# FPGA_S6.net
KiCad netlist of a schematic drawn in EAGLE
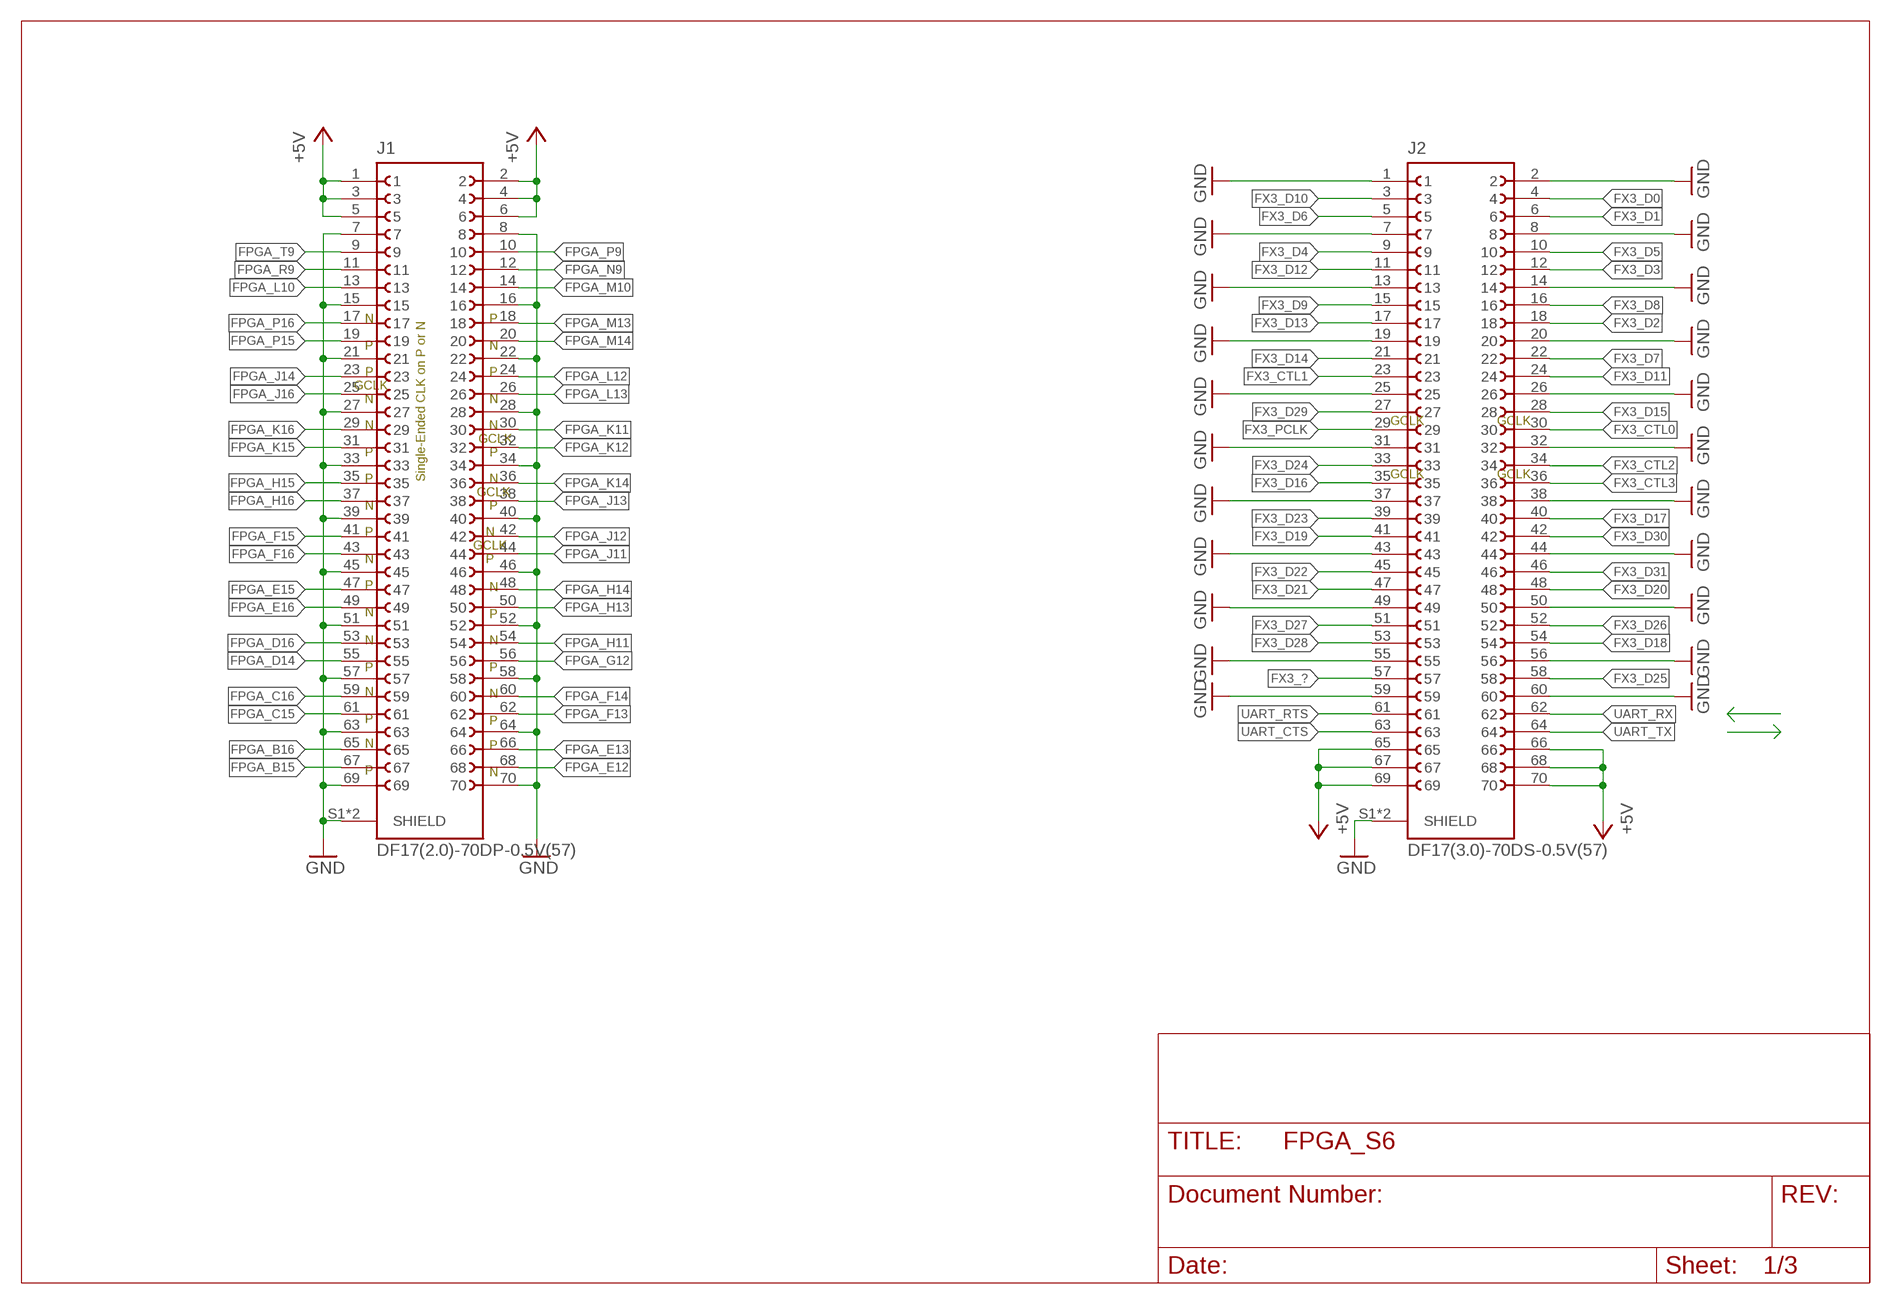
[diagram p0: schematic, sheet 1]
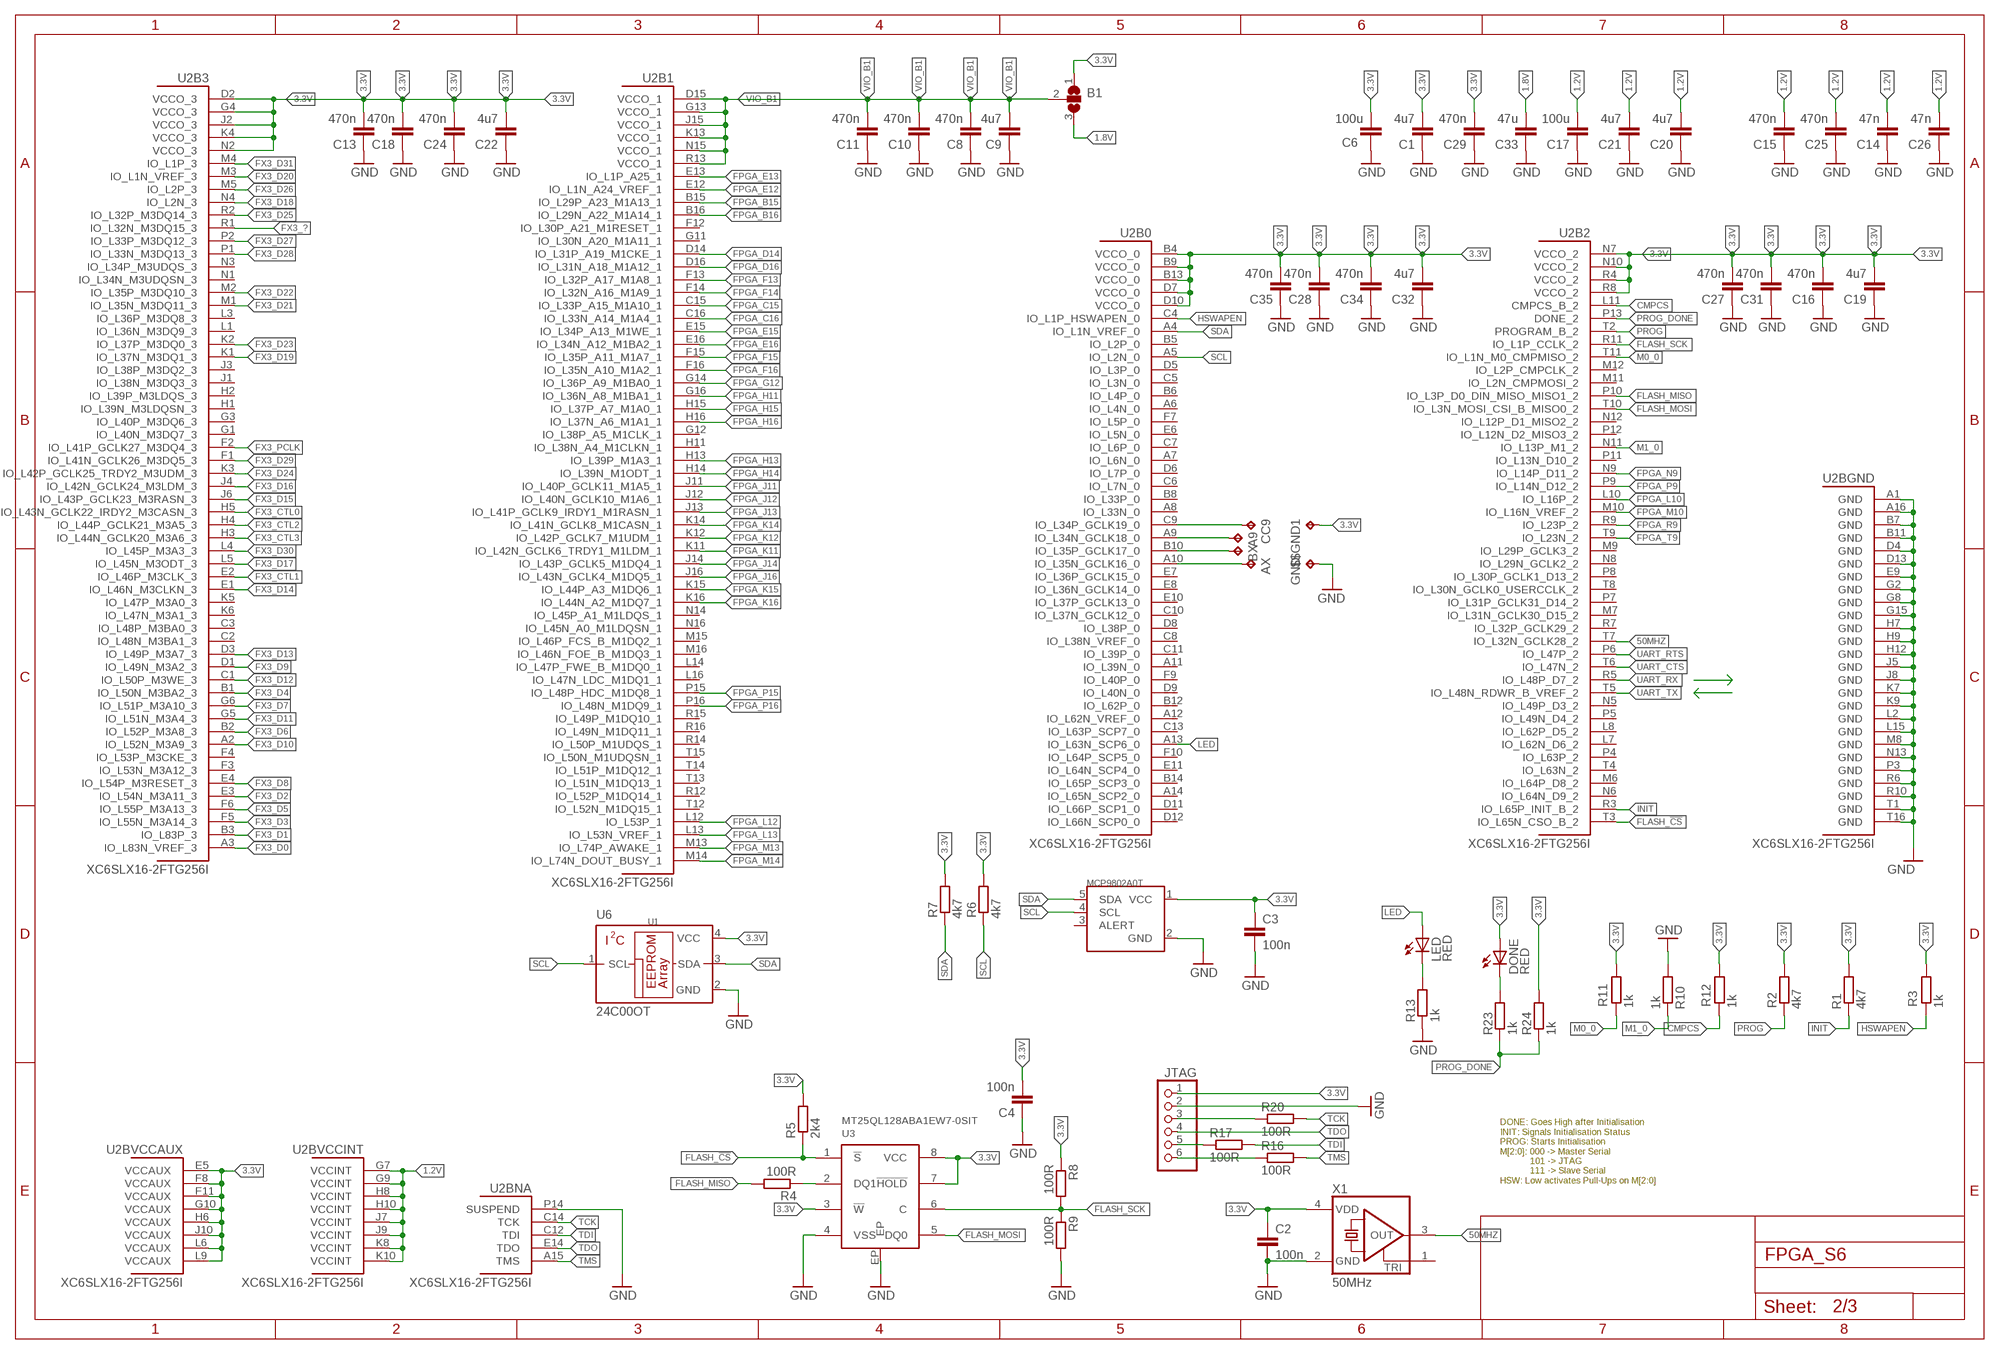
[diagram p1: schematic, sheet 2]
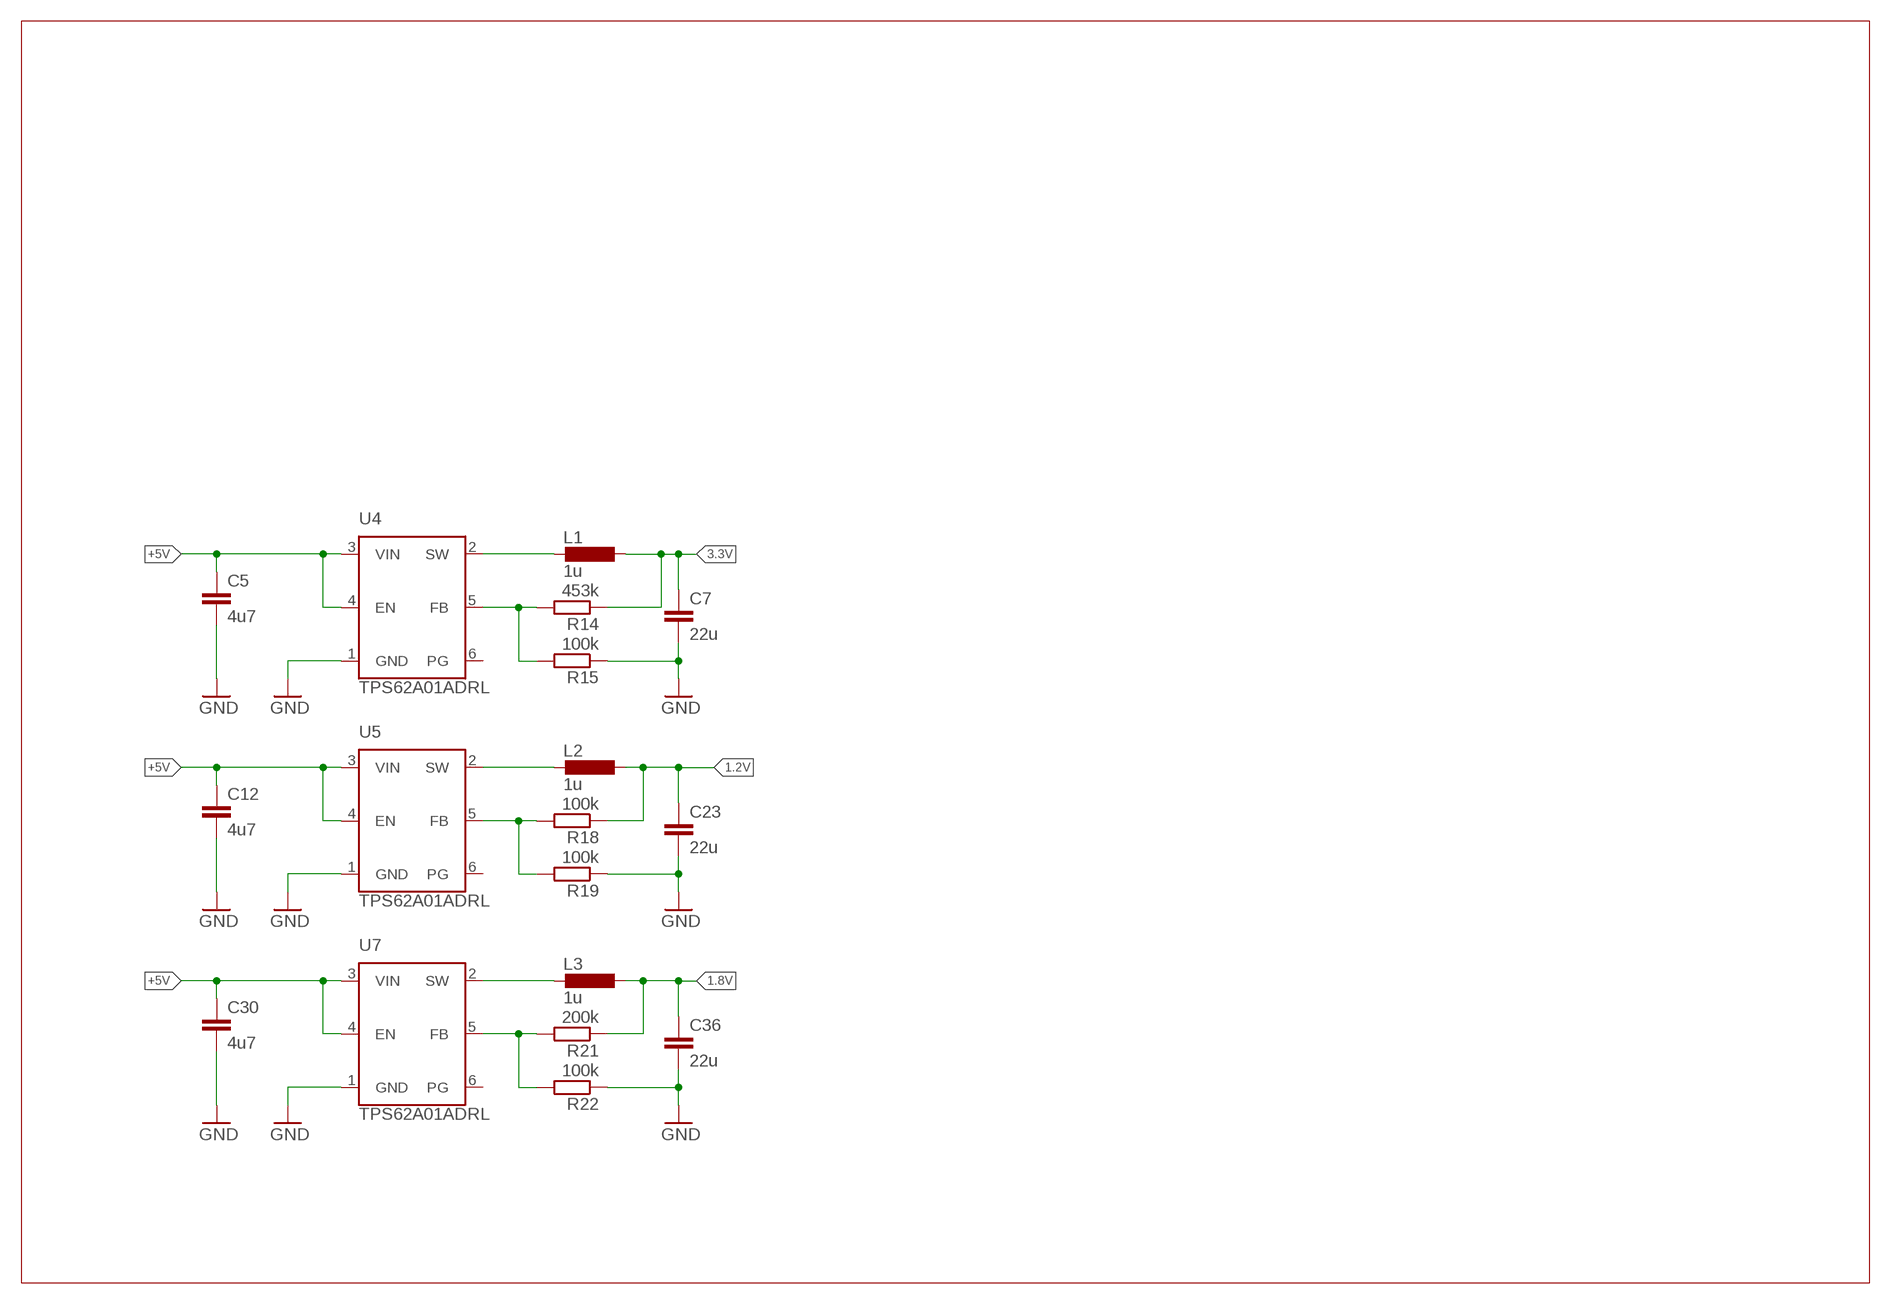
[diagram p2: schematic, sheet 3]

(export (version "E")
  (design (tool "Eeschema 10.0.6"))
  (components
    (comp (ref "$$GND1")
      (value "TPTP15R")
      (footprint "eagle-import:TP15R")
      (libsource (lib "eagle-import") (part "TPTP15R"))
    )
    (comp (ref "A9")
      (value "TPTP15R")
      (footprint "eagle-import:TP15R")
      (libsource (lib "eagle-import") (part "TPTP15R"))
    )
    (comp (ref "AX")
      (value "TPTP15R")
      (footprint "eagle-import:TP15R")
      (libsource (lib "eagle-import") (part "TPTP15R"))
    )
    (comp (ref "B1")
      (value "SJ2W")
      (footprint "eagle-import:SJ_2")
      (libsource (lib "eagle-import") (part "SJ2W"))
    )
    (comp (ref "BX")
      (value "TPTP15R")
      (footprint "eagle-import:TP15R")
      (libsource (lib "eagle-import") (part "TPTP15R"))
    )
    (comp (ref "C1")
      (value "4u7")
      (footprint "eagle-import:C0603")
      (libsource (lib "eagle-import") (part "C-EUC0603"))
    )
    (comp (ref "C2")
      (value "100n")
      (footprint "eagle-import:C0402")
      (libsource (lib "eagle-import") (part "C-EUC0402"))
    )
    (comp (ref "C3")
      (value "100n")
      (footprint "eagle-import:C0402")
      (libsource (lib "eagle-import") (part "C-EUC0402"))
    )
    (comp (ref "C4")
      (value "100n")
      (footprint "eagle-import:C0402")
      (libsource (lib "eagle-import") (part "C-EUC0402"))
    )
    (comp (ref "C6")
      (value "100u")
      (footprint "eagle-import:C1206")
      (libsource (lib "eagle-import") (part "rcl_334_C-EUC1206"))
    )
    (comp (ref "C8")
      (value "470n")
      (footprint "eagle-import:C0402")
      (libsource (lib "eagle-import") (part "C-EUC0402"))
    )
    (comp (ref "C9")
      (value "4u7")
      (footprint "eagle-import:C0603")
      (libsource (lib "eagle-import") (part "C-EUC0603"))
    )
    (comp (ref "C10")
      (value "470n")
      (footprint "eagle-import:C0402")
      (libsource (lib "eagle-import") (part "C-EUC0402"))
    )
    (comp (ref "C11")
      (value "470n")
      (footprint "eagle-import:C0402")
      (libsource (lib "eagle-import") (part "C-EUC0402"))
    )
    (comp (ref "C13")
      (value "470n")
      (footprint "eagle-import:C0402")
      (libsource (lib "eagle-import") (part "C-EUC0402"))
    )
    (comp (ref "C14")
      (value "47n")
      (footprint "eagle-import:C0402")
      (libsource (lib "eagle-import") (part "C-EUC0402"))
    )
    (comp (ref "C15")
      (value "470n")
      (footprint "eagle-import:C0402")
      (libsource (lib "eagle-import") (part "C-EUC0402"))
    )
    (comp (ref "C16")
      (value "470n")
      (footprint "eagle-import:C0402")
      (libsource (lib "eagle-import") (part "C-EUC0402"))
    )
    (comp (ref "C17")
      (value "100u")
      (footprint "eagle-import:C1206")
      (libsource (lib "eagle-import") (part "rcl_334_C-EUC1206"))
    )
    (comp (ref "C18")
      (value "470n")
      (footprint "eagle-import:C0402")
      (libsource (lib "eagle-import") (part "C-EUC0402"))
    )
    (comp (ref "C19")
      (value "4u7")
      (footprint "eagle-import:C0603")
      (libsource (lib "eagle-import") (part "C-EUC0603"))
    )
    (comp (ref "C20")
      (value "4u7")
      (footprint "eagle-import:C0603")
      (libsource (lib "eagle-import") (part "C-EUC0603"))
    )
    (comp (ref "C21")
      (value "4u7")
      (footprint "eagle-import:C0603")
      (libsource (lib "eagle-import") (part "C-EUC0603"))
    )
    (comp (ref "C22")
      (value "4u7")
      (footprint "eagle-import:C0603")
      (libsource (lib "eagle-import") (part "C-EUC0603"))
    )
    (comp (ref "C24")
      (value "470n")
      (footprint "eagle-import:C0402")
      (libsource (lib "eagle-import") (part "C-EUC0402"))
    )
    (comp (ref "C25")
      (value "470n")
      (footprint "eagle-import:C0402")
      (libsource (lib "eagle-import") (part "C-EUC0402"))
    )
    (comp (ref "C26")
      (value "47n")
      (footprint "eagle-import:C0402")
      (libsource (lib "eagle-import") (part "C-EUC0402"))
    )
    (comp (ref "C27")
      (value "470n")
      (footprint "eagle-import:C0402")
      (libsource (lib "eagle-import") (part "C-EUC0402"))
    )
    (comp (ref "C28")
      (value "470n")
      (footprint "eagle-import:C0402")
      (libsource (lib "eagle-import") (part "C-EUC0402"))
    )
    (comp (ref "C29")
      (value "470n")
      (footprint "eagle-import:C0402")
      (libsource (lib "eagle-import") (part "C-EUC0402"))
    )
    (comp (ref "C31")
      (value "470n")
      (footprint "eagle-import:C0402")
      (libsource (lib "eagle-import") (part "C-EUC0402"))
    )
    (comp (ref "C32")
      (value "4u7")
      (footprint "eagle-import:C0603")
      (libsource (lib "eagle-import") (part "C-EUC0603"))
    )
    (comp (ref "C33")
      (value "47u")
      (footprint "eagle-import:C0805")
      (libsource (lib "eagle-import") (part "C-EUC0805"))
    )
    (comp (ref "C34")
      (value "470n")
      (footprint "eagle-import:C0402")
      (libsource (lib "eagle-import") (part "C-EUC0402"))
    )
    (comp (ref "C35")
      (value "470n")
      (footprint "eagle-import:C0402")
      (libsource (lib "eagle-import") (part "C-EUC0402"))
    )
    (comp (ref "CC9")
      (value "TPTP15R")
      (footprint "eagle-import:TP15R")
      (libsource (lib "eagle-import") (part "TPTP15R"))
    )
    (comp (ref "DONE")
      (value "RED")
      (footprint "eagle-import:CHIP-LED0603")
      (libsource (lib "eagle-import") (part "LEDCHIP-LED0603"))
    )
    (comp (ref "GND")
      (value "TPTP15R")
      (footprint "eagle-import:TP15R")
      (libsource (lib "eagle-import") (part "TPTP15R"))
    )
    (comp (ref "JTAG")
      (value "PINHD-1X6_2.00")
      (footprint "eagle-import:1X06M")
      (libsource (lib "eagle-import") (part "PINHD-1X6_2.00"))
    )
    (comp (ref "LED")
      (value "RED")
      (footprint "eagle-import:CHIP-LED0603")
      (libsource (lib "eagle-import") (part "LEDCHIP-LED0603"))
    )
    (comp (ref "R1")
      (value "4k7")
      (footprint "eagle-import:R0402")
      (libsource (lib "eagle-import") (part "R-EU_R0402"))
    )
    (comp (ref "R2")
      (value "4k7")
      (footprint "eagle-import:R0402")
      (libsource (lib "eagle-import") (part "R-EU_R0402"))
    )
    (comp (ref "R3")
      (value "1k")
      (footprint "eagle-import:R0402")
      (libsource (lib "eagle-import") (part "R-EU_R0402"))
    )
    (comp (ref "R4")
      (value "100R")
      (footprint "eagle-import:R0402")
      (libsource (lib "eagle-import") (part "R-EU_R0402"))
    )
    (comp (ref "R5")
      (value "2k4")
      (footprint "eagle-import:R0402")
      (libsource (lib "eagle-import") (part "R-EU_R0402"))
    )
    (comp (ref "R6")
      (value "4k7")
      (footprint "eagle-import:R0402")
      (libsource (lib "eagle-import") (part "R-EU_R0402"))
    )
    (comp (ref "R7")
      (value "4k7")
      (footprint "eagle-import:R0402")
      (libsource (lib "eagle-import") (part "R-EU_R0402"))
    )
    (comp (ref "R8")
      (value "100R")
      (footprint "eagle-import:R0402")
      (libsource (lib "eagle-import") (part "R-EU_R0402"))
    )
    (comp (ref "R9")
      (value "100R")
      (footprint "eagle-import:R0402")
      (libsource (lib "eagle-import") (part "R-EU_R0402"))
    )
    (comp (ref "R10")
      (value "1k")
      (footprint "eagle-import:R0402")
      (libsource (lib "eagle-import") (part "R-EU_R0402"))
    )
    (comp (ref "R11")
      (value "1k")
      (footprint "eagle-import:R0402")
      (libsource (lib "eagle-import") (part "R-EU_R0402"))
    )
    (comp (ref "R12")
      (value "1k")
      (footprint "eagle-import:R0402")
      (libsource (lib "eagle-import") (part "R-EU_R0402"))
    )
    (comp (ref "R13")
      (value "1k")
      (footprint "eagle-import:R0402")
      (libsource (lib "eagle-import") (part "R-EU_R0402"))
    )
    (comp (ref "R16")
      (value "100R")
      (footprint "eagle-import:R0402")
      (libsource (lib "eagle-import") (part "R-EU_R0402"))
    )
    (comp (ref "R17")
      (value "100R")
      (footprint "eagle-import:R0402")
      (libsource (lib "eagle-import") (part "R-EU_R0402"))
    )
    (comp (ref "R20")
      (value "100R")
      (footprint "eagle-import:R0402")
      (libsource (lib "eagle-import") (part "R-EU_R0402"))
    )
    (comp (ref "R23")
      (value "1k")
      (footprint "eagle-import:R0402")
      (libsource (lib "eagle-import") (part "R-EU_R0402"))
    )
    (comp (ref "R24")
      (value "1k")
      (footprint "eagle-import:R0402")
      (libsource (lib "eagle-import") (part "R-EU_R0402"))
    )
    (comp (ref "U1")
      (value "MCP9802A0T")
      (footprint "eagle-import:SOT23-5L")
      (libsource (lib "eagle-import") (part "MCP9802A0T"))
    )
    (comp (ref "U2")
      (value "XC6SLX16-2FTG256I")
      (footprint "eagle-import:FT256")
      (fields (field (name "DIGIKEY") "122-1752-ND ") (field (name "MBM") "1") (field (name "PREIS") "29,4"))
      (libsource (lib "eagle-import") (part "6SLX16FTG256"))
    )
    (comp (ref "U3")
      (value "MT25QL128ABA1EW7-0SIT")
      (footprint "eagle-import:MT25QL128ABA1EW7-0SIT")
      (libsource (lib "eagle-import") (part "MT25Q"))
    )
    (comp (ref "U6")
      (value "24C00OT")
      (footprint "eagle-import:SOT23-5L")
      (fields (field (name "MF") "MICROCHIP") (field (name "MPN") "24C00T-I/OT"))
      (libsource (lib "eagle-import") (part "2400OTC"))
    )
    (comp (ref "X1")
      (value "50MHz")
      (footprint "eagle-import:ASE")
      (libsource (lib "eagle-import") (part "ASE"))
    )
    (comp (ref "C5")
      (value "4u7")
      (footprint "eagle-import:C0603")
      (libsource (lib "eagle-import") (part "C-EUC0603"))
    )
    (comp (ref "C7")
      (value "22u")
      (footprint "eagle-import:C0603")
      (libsource (lib "eagle-import") (part "C-EUC0603"))
    )
    (comp (ref "C12")
      (value "4u7")
      (footprint "eagle-import:C0603")
      (libsource (lib "eagle-import") (part "C-EUC0603"))
    )
    (comp (ref "C23")
      (value "22u")
      (footprint "eagle-import:C0603")
      (libsource (lib "eagle-import") (part "C-EUC0603"))
    )
    (comp (ref "C30")
      (value "4u7")
      (footprint "eagle-import:C0603")
      (libsource (lib "eagle-import") (part "C-EUC0603"))
    )
    (comp (ref "C36")
      (value "22u")
      (footprint "eagle-import:C0603")
      (libsource (lib "eagle-import") (part "C-EUC0603"))
    )
    (comp (ref "L1")
      (value "1u")
      (footprint "eagle-import:L1008")
      (fields (field (name "MPN") "LQM2HPN1R0MG0L"))
      (libsource (lib "eagle-import") (part "L-EU1008"))
    )
    (comp (ref "L2")
      (value "1u")
      (footprint "eagle-import:L1008")
      (fields (field (name "MPN") "LQM2HPN1R0MG0L"))
      (libsource (lib "eagle-import") (part "L-EU1008"))
    )
    (comp (ref "L3")
      (value "1u")
      (footprint "eagle-import:L1008")
      (fields (field (name "MPN") "LQM2HPN1R0MG0L"))
      (libsource (lib "eagle-import") (part "L-EU1008"))
    )
    (comp (ref "R14")
      (value "453k")
      (footprint "eagle-import:R0402")
      (libsource (lib "eagle-import") (part "rcl_334_R-EU_R0402"))
    )
    (comp (ref "R15")
      (value "100k")
      (footprint "eagle-import:R0402")
      (libsource (lib "eagle-import") (part "rcl_334_R-EU_R0402"))
    )
    (comp (ref "R18")
      (value "100k")
      (footprint "eagle-import:R0402")
      (libsource (lib "eagle-import") (part "rcl_334_R-EU_R0402"))
    )
    (comp (ref "R19")
      (value "100k")
      (footprint "eagle-import:R0402")
      (libsource (lib "eagle-import") (part "rcl_334_R-EU_R0402"))
    )
    (comp (ref "R21")
      (value "200k")
      (footprint "eagle-import:R0402")
      (libsource (lib "eagle-import") (part "rcl_334_R-EU_R0402"))
    )
    (comp (ref "R22")
      (value "100k")
      (footprint "eagle-import:R0402")
      (libsource (lib "eagle-import") (part "rcl_334_R-EU_R0402"))
    )
    (comp (ref "U4")
      (value "TPS62A01ADRL")
      (footprint "eagle-import:SOTFL50P160X60-6N")
      (fields (field (name "MANUFACTURER_PART_NUMBER") "TPS62A01ADRLR"))
      (libsource (lib "eagle-import") (part "TPS62A01ADRL"))
    )
    (comp (ref "U5")
      (value "TPS62A01ADRL")
      (footprint "eagle-import:SOTFL50P160X60-6N")
      (fields (field (name "MANUFACTURER_PART_NUMBER") "TPS62A01ADRLR"))
      (libsource (lib "eagle-import") (part "TPS62A01ADRL"))
    )
    (comp (ref "U7")
      (value "TPS62A01ADRL")
      (footprint "eagle-import:SOTFL50P160X60-6N")
      (fields (field (name "MANUFACTURER_PART_NUMBER") "TPS62A01ADRLR"))
      (libsource (lib "eagle-import") (part "TPS62A01ADRL"))
    )
    (comp (ref "J1")
      (value "DF17(2.0)-70DP-0.5V(57)")
      (footprint "eagle-import:DF17(2.0)-70DP-0.5V(57)")
      (libsource (lib "eagle-import") (part "DF17(2.0)-70DP-0.5V(57)"))
    )
    (comp (ref "J2")
      (value "DF17(3.0)-70DS-0.5V(57)")
      (footprint "eagle-import:DF17(3.0)-70DS-0.5V(57)")
      (libsource (lib "eagle-import") (part "DF17(3.0)-70DS-0.5V(57)"))
    )
  )
  (nets
    (net (code "1") (name "+5V") (class "Default")
      (node (ref "C12") (pin "1") (pinfunction "1_1") (pintype "passive"))
      (node (ref "C30") (pin "1") (pinfunction "1_1") (pintype "passive"))
      (node (ref "C5") (pin "1") (pinfunction "1_1") (pintype "passive"))
      (node (ref "J1") (pin "1") (pinfunction "1_1") (pintype "passive"))
      (node (ref "J1") (pin "2") (pinfunction "2_2") (pintype "passive"))
      (node (ref "J1") (pin "3") (pinfunction "3_3") (pintype "passive"))
      (node (ref "J1") (pin "4") (pinfunction "4_4") (pintype "passive"))
      (node (ref "J1") (pin "5") (pinfunction "5_5") (pintype "passive"))
      (node (ref "J1") (pin "6") (pinfunction "6_6") (pintype "passive"))
      (node (ref "J2") (pin "65") (pinfunction "65_65") (pintype "passive"))
      (node (ref "J2") (pin "66") (pinfunction "66_66") (pintype "passive"))
      (node (ref "J2") (pin "67") (pinfunction "67_67") (pintype "passive"))
      (node (ref "J2") (pin "68") (pinfunction "68_68") (pintype "passive"))
      (node (ref "J2") (pin "69") (pinfunction "69_69") (pintype "passive"))
      (node (ref "J2") (pin "70") (pinfunction "70_70") (pintype "passive"))
      (node (ref "U4") (pin "3") (pinfunction "VIN_3") (pintype "bidirectional"))
      (node (ref "U4") (pin "4") (pinfunction "EN_4") (pintype "bidirectional"))
      (node (ref "U5") (pin "3") (pinfunction "VIN_3") (pintype "bidirectional"))
      (node (ref "U5") (pin "4") (pinfunction "EN_4") (pintype "bidirectional"))
      (node (ref "U7") (pin "3") (pinfunction "VIN_3") (pintype "bidirectional"))
      (node (ref "U7") (pin "4") (pinfunction "EN_4") (pintype "bidirectional"))
    )
    (net (code "2") (name "1.2V") (class "Default")
      (node (ref "C14") (pin "2") (pinfunction "2_2") (pintype "passive"))
      (node (ref "C15") (pin "2") (pinfunction "2_2") (pintype "passive"))
      (node (ref "C17") (pin "1") (pinfunction "1_1") (pintype "passive"))
      (node (ref "C20") (pin "2") (pinfunction "2_2") (pintype "passive"))
      (node (ref "C21") (pin "2") (pinfunction "2_2") (pintype "passive"))
      (node (ref "C23") (pin "1") (pinfunction "1_1") (pintype "passive"))
      (node (ref "C25") (pin "2") (pinfunction "2_2") (pintype "passive"))
      (node (ref "C26") (pin "2") (pinfunction "2_2") (pintype "passive"))
      (node (ref "L2") (pin "1") (pinfunction "1_1") (pintype "passive"))
      (node (ref "R18") (pin "1") (pinfunction "1_1") (pintype "passive"))
      (node (ref "U2") (pin "G7") (pinfunction "VCCINT_G7") (pintype "input"))
      (node (ref "U2") (pin "G9") (pinfunction "VCCINT_G9") (pintype "input"))
      (node (ref "U2") (pin "H10") (pinfunction "VCCINT_H10") (pintype "input"))
      (node (ref "U2") (pin "H8") (pinfunction "VCCINT_H8") (pintype "input"))
      (node (ref "U2") (pin "J7") (pinfunction "VCCINT_J7") (pintype "input"))
      (node (ref "U2") (pin "J9") (pinfunction "VCCINT_J9") (pintype "input"))
      (node (ref "U2") (pin "K10") (pinfunction "VCCINT_K10") (pintype "input"))
      (node (ref "U2") (pin "K8") (pinfunction "VCCINT_K8") (pintype "input"))
    )
    (net (code "3") (name "1.8V") (class "Default")
      (node (ref "B1") (pin "3") (pinfunction "3_3") (pintype "passive"))
      (node (ref "C33") (pin "2") (pinfunction "2_2") (pintype "passive"))
      (node (ref "C36") (pin "1") (pinfunction "1_1") (pintype "passive"))
      (node (ref "L3") (pin "1") (pinfunction "1_1") (pintype "passive"))
      (node (ref "R21") (pin "1") (pinfunction "1_1") (pintype "passive"))
    )
    (net (code "4") (name "3.3V") (class "Default")
      (node (ref "$$GND1") (pin "TP") (pinfunction "TP_TP") (pintype "input"))
      (node (ref "B1") (pin "1") (pinfunction "1_1") (pintype "passive"))
      (node (ref "C1") (pin "2") (pinfunction "2_2") (pintype "passive"))
      (node (ref "C13") (pin "2") (pinfunction "2_2") (pintype "passive"))
      (node (ref "C16") (pin "2") (pinfunction "2_2") (pintype "passive"))
      (node (ref "C18") (pin "2") (pinfunction "2_2") (pintype "passive"))
      (node (ref "C19") (pin "2") (pinfunction "2_2") (pintype "passive"))
      (node (ref "C2") (pin "1") (pinfunction "1_1") (pintype "passive"))
      (node (ref "C22") (pin "2") (pinfunction "2_2") (pintype "passive"))
      (node (ref "C24") (pin "2") (pinfunction "2_2") (pintype "passive"))
      (node (ref "C27") (pin "2") (pinfunction "2_2") (pintype "passive"))
      (node (ref "C28") (pin "2") (pinfunction "2_2") (pintype "passive"))
      (node (ref "C29") (pin "2") (pinfunction "2_2") (pintype "passive"))
      (node (ref "C3") (pin "1") (pinfunction "1_1") (pintype "passive"))
      (node (ref "C31") (pin "2") (pinfunction "2_2") (pintype "passive"))
      (node (ref "C32") (pin "2") (pinfunction "2_2") (pintype "passive"))
      (node (ref "C34") (pin "2") (pinfunction "2_2") (pintype "passive"))
      (node (ref "C35") (pin "2") (pinfunction "2_2") (pintype "passive"))
      (node (ref "C4") (pin "2") (pinfunction "2_2") (pintype "passive"))
      (node (ref "C6") (pin "1") (pinfunction "1_1") (pintype "passive"))
      (node (ref "C7") (pin "1") (pinfunction "1_1") (pintype "passive"))
      (node (ref "DONE") (pin "A") (pinfunction "A_A") (pintype "passive"))
      (node (ref "JTAG") (pin "1") (pinfunction "1_1") (pintype "passive"))
      (node (ref "L1") (pin "1") (pinfunction "1_1") (pintype "passive"))
      (node (ref "R1") (pin "2") (pinfunction "2_2") (pintype "passive"))
      (node (ref "R11") (pin "1") (pinfunction "1_1") (pintype "passive"))
      (node (ref "R12") (pin "1") (pinfunction "1_1") (pintype "passive"))
      (node (ref "R14") (pin "1") (pinfunction "1_1") (pintype "passive"))
      (node (ref "R2") (pin "1") (pinfunction "1_1") (pintype "passive"))
      (node (ref "R24") (pin "2") (pinfunction "2_2") (pintype "passive"))
      (node (ref "R3") (pin "1") (pinfunction "1_1") (pintype "passive"))
      (node (ref "R5") (pin "2") (pinfunction "2_2") (pintype "passive"))
      (node (ref "R6") (pin "1") (pinfunction "1_1") (pintype "passive"))
      (node (ref "R7") (pin "1") (pinfunction "1_1") (pintype "passive"))
      (node (ref "R8") (pin "1") (pinfunction "1_1") (pintype "passive"))
      (node (ref "U1") (pin "1") (pinfunction "VCC_1") (pintype "power_in"))
      (node (ref "U2") (pin "B13") (pinfunction "VCCO_0_B13") (pintype "input"))
      (node (ref "U2") (pin "B4") (pinfunction "VCCO_0_B4") (pintype "input"))
      (node (ref "U2") (pin "B9") (pinfunction "VCCO_0_B9") (pintype "input"))
      (node (ref "U2") (pin "D10") (pinfunction "VCCO_0_D10") (pintype "input"))
      (node (ref "U2") (pin "D2") (pinfunction "VCCO_3_D2") (pintype "input"))
      (node (ref "U2") (pin "D7") (pinfunction "VCCO_0_D7") (pintype "input"))
      (node (ref "U2") (pin "E5") (pinfunction "VCCAUX_E5") (pintype "input"))
      (node (ref "U2") (pin "F11") (pinfunction "VCCAUX_F11") (pintype "input"))
      (node (ref "U2") (pin "F8") (pinfunction "VCCAUX_F8") (pintype "input"))
      (node (ref "U2") (pin "G10") (pinfunction "VCCAUX_G10") (pintype "input"))
      (node (ref "U2") (pin "G4") (pinfunction "VCCO_3_G4") (pintype "input"))
      (node (ref "U2") (pin "H6") (pinfunction "VCCAUX_H6") (pintype "input"))
      (node (ref "U2") (pin "J10") (pinfunction "VCCAUX_J10") (pintype "input"))
      (node (ref "U2") (pin "J2") (pinfunction "VCCO_3_J2") (pintype "input"))
      (node (ref "U2") (pin "K4") (pinfunction "VCCO_3_K4") (pintype "input"))
      (node (ref "U2") (pin "L6") (pinfunction "VCCAUX_L6") (pintype "input"))
      (node (ref "U2") (pin "L9") (pinfunction "VCCAUX_L9") (pintype "input"))
      (node (ref "U2") (pin "N10") (pinfunction "VCCO_2_N10") (pintype "input"))
      (node (ref "U2") (pin "N2") (pinfunction "VCCO_3_N2") (pintype "input"))
      (node (ref "U2") (pin "N7") (pinfunction "VCCO_2_N7") (pintype "input"))
      (node (ref "U2") (pin "R4") (pinfunction "VCCO_2_R4") (pintype "input"))
      (node (ref "U2") (pin "R8") (pinfunction "VCCO_2_R8") (pintype "input"))
      (node (ref "U3") (pin "3") (pinfunction "~{W}_3") (pintype "bidirectional"))
      (node (ref "U3") (pin "7") (pinfunction "~{HOLD}_7") (pintype "bidirectional"))
      (node (ref "U3") (pin "8") (pinfunction "VCC_8") (pintype "bidirectional"))
      (node (ref "U6") (pin "4") (pinfunction "VCC_4") (pintype "power_in"))
      (node (ref "X1") (pin "4") (pinfunction "VDD_4") (pintype "power_in"))
    )
    (net (code "5") (name "50MHZ") (class "Default")
      (node (ref "U2") (pin "T7") (pinfunction "IO_L32N_GCLK28_2_T7") (pintype "bidirectional"))
      (node (ref "X1") (pin "3") (pinfunction "OUT_3") (pintype "output"))
    )
    (net (code "6") (name "CMPCS") (class "Default")
      (node (ref "R12") (pin "2") (pinfunction "2_2") (pintype "passive"))
      (node (ref "U2") (pin "L11") (pinfunction "CMPCS_B_2_L11") (pintype "bidirectional"))
    )
    (net (code "7") (name "FLASH_MISO") (class "Default")
      (node (ref "R4") (pin "2") (pinfunction "2_2") (pintype "passive"))
      (node (ref "U2") (pin "P10") (pinfunction "IO_L3P_D0_DIN_MISO_MISO1_2_P10") (pintype "bidirectional"))
    )
    (net (code "8") (name "FLASH_MOSI") (class "Default")
      (node (ref "U2") (pin "T10") (pinfunction "IO_L3N_MOSI_CSI_B_MISO0_2_T10") (pintype "bidirectional"))
      (node (ref "U3") (pin "5") (pinfunction "DQ0_5") (pintype "bidirectional"))
    )
    (net (code "9") (name "FLASH_SCK") (class "Default")
      (node (ref "R8") (pin "2") (pinfunction "2_2") (pintype "passive"))
      (node (ref "R9") (pin "1") (pinfunction "1_1") (pintype "passive"))
      (node (ref "U2") (pin "R11") (pinfunction "IO_L1P_CCLK_2_R11") (pintype "bidirectional"))
      (node (ref "U3") (pin "6") (pinfunction "C_6") (pintype "bidirectional"))
    )
    (net (code "10") (name "FLASH_~{CS}") (class "Default")
      (node (ref "R5") (pin "1") (pinfunction "1_1") (pintype "passive"))
      (node (ref "U2") (pin "T3") (pinfunction "IO_L65N_CSO_B_2_T3") (pintype "bidirectional"))
      (node (ref "U3") (pin "1") (pinfunction "~{S}_1") (pintype "bidirectional"))
    )
    (net (code "11") (name "FPGA_B15") (class "Default")
      (node (ref "J1") (pin "67") (pinfunction "67_67") (pintype "passive"))
      (node (ref "U2") (pin "B15") (pinfunction "IO_L29P_A23_M1A13_1_B15") (pintype "bidirectional"))
    )
    (net (code "12") (name "FPGA_B16") (class "Default")
      (node (ref "J1") (pin "65") (pinfunction "65_65") (pintype "passive"))
      (node (ref "U2") (pin "B16") (pinfunction "IO_L29N_A22_M1A14_1_B16") (pintype "bidirectional"))
    )
    (net (code "13") (name "FPGA_C15") (class "Default")
      (node (ref "J1") (pin "61") (pinfunction "61_61") (pintype "passive"))
      (node (ref "U2") (pin "C15") (pinfunction "IO_L33P_A15_M1A10_1_C15") (pintype "bidirectional"))
    )
    (net (code "14") (name "FPGA_C16") (class "Default")
      (node (ref "J1") (pin "59") (pinfunction "59_59") (pintype "passive"))
      (node (ref "U2") (pin "C16") (pinfunction "IO_L33N_A14_M1A4_1_C16") (pintype "bidirectional"))
    )
    (net (code "15") (name "FPGA_D14") (class "Default")
      (node (ref "J1") (pin "55") (pinfunction "55_55") (pintype "passive"))
      (node (ref "U2") (pin "D14") (pinfunction "IO_L31P_A19_M1CKE_1_D14") (pintype "bidirectional"))
    )
    (net (code "16") (name "FPGA_D16") (class "Default")
      (node (ref "J1") (pin "53") (pinfunction "53_53") (pintype "passive"))
      (node (ref "U2") (pin "D16") (pinfunction "IO_L31N_A18_M1A12_1_D16") (pintype "bidirectional"))
    )
    (net (code "17") (name "FPGA_E12") (class "Default")
      (node (ref "J1") (pin "68") (pinfunction "68_68") (pintype "passive"))
      (node (ref "U2") (pin "E12") (pinfunction "IO_L1N_A24_VREF_1_E12") (pintype "bidirectional"))
    )
    (net (code "18") (name "FPGA_E13") (class "Default")
      (node (ref "J1") (pin "66") (pinfunction "66_66") (pintype "passive"))
      (node (ref "U2") (pin "E13") (pinfunction "IO_L1P_A25_1_E13") (pintype "bidirectional"))
    )
    (net (code "19") (name "FPGA_E15") (class "Default")
      (node (ref "J1") (pin "47") (pinfunction "47_47") (pintype "passive"))
      (node (ref "U2") (pin "E15") (pinfunction "IO_L34P_A13_M1WE_1_E15") (pintype "bidirectional"))
    )
    (net (code "20") (name "FPGA_E16") (class "Default")
      (node (ref "J1") (pin "49") (pinfunction "49_49") (pintype "passive"))
      (node (ref "U2") (pin "E16") (pinfunction "IO_L34N_A12_M1BA2_1_E16") (pintype "bidirectional"))
    )
    (net (code "21") (name "FPGA_F13") (class "Default")
      (node (ref "J1") (pin "62") (pinfunction "62_62") (pintype "passive"))
      (node (ref "U2") (pin "F13") (pinfunction "IO_L32P_A17_M1A8_1_F13") (pintype "bidirectional"))
    )
    (net (code "22") (name "FPGA_F14") (class "Default")
      (node (ref "J1") (pin "60") (pinfunction "60_60") (pintype "passive"))
      (node (ref "U2") (pin "F14") (pinfunction "IO_L32N_A16_M1A9_1_F14") (pintype "bidirectional"))
    )
    (net (code "23") (name "FPGA_F15") (class "Default")
      (node (ref "J1") (pin "41") (pinfunction "41_41") (pintype "passive"))
      (node (ref "U2") (pin "F15") (pinfunction "IO_L35P_A11_M1A7_1_F15") (pintype "bidirectional"))
    )
    (net (code "24") (name "FPGA_F16") (class "Default")
      (node (ref "J1") (pin "43") (pinfunction "43_43") (pintype "passive"))
      (node (ref "U2") (pin "F16") (pinfunction "IO_L35N_A10_M1A2_1_F16") (pintype "bidirectional"))
    )
    (net (code "25") (name "FPGA_G12") (class "Default")
      (node (ref "J1") (pin "56") (pinfunction "56_56") (pintype "passive"))
      (node (ref "U2") (pin "G14") (pinfunction "IO_L36P_A9_M1BA0_1_G14") (pintype "bidirectional"))
    )
    (net (code "26") (name "FPGA_H11") (class "Default")
      (node (ref "J1") (pin "54") (pinfunction "54_54") (pintype "passive"))
      (node (ref "U2") (pin "G16") (pinfunction "IO_L36N_A8_M1BA1_1_G16") (pintype "bidirectional"))
    )
    (net (code "27") (name "FPGA_H13") (class "Default")
      (node (ref "J1") (pin "50") (pinfunction "50_50") (pintype "passive"))
      (node (ref "U2") (pin "H13") (pinfunction "IO_L39P_M1A3_1_H13") (pintype "bidirectional"))
    )
    (net (code "28") (name "FPGA_H14") (class "Default")
      (node (ref "J1") (pin "48") (pinfunction "48_48") (pintype "passive"))
      (node (ref "U2") (pin "H14") (pinfunction "IO_L39N_M1ODT_1_H14") (pintype "bidirectional"))
    )
    (net (code "29") (name "FPGA_H15") (class "Default")
      (node (ref "J1") (pin "35") (pinfunction "35_35") (pintype "passive"))
      (node (ref "U2") (pin "H15") (pinfunction "IO_L37P_A7_M1A0_1_H15") (pintype "bidirectional"))
    )
    (net (code "30") (name "FPGA_H16") (class "Default")
      (node (ref "J1") (pin "37") (pinfunction "37_37") (pintype "passive"))
      (node (ref "U2") (pin "H16") (pinfunction "IO_L37N_A6_M1A1_1_H16") (pintype "bidirectional"))
    )
    (net (code "31") (name "FPGA_J11") (class "Default")
      (node (ref "J1") (pin "44") (pinfunction "44_44") (pintype "passive"))
      (node (ref "U2") (pin "J11") (pinfunction "IO_L40P_GCLK11_M1A5_1_J11") (pintype "bidirectional"))
    )
    (net (code "32") (name "FPGA_J12") (class "Default")
      (node (ref "J1") (pin "42") (pinfunction "42_42") (pintype "passive"))
      (node (ref "U2") (pin "J12") (pinfunction "IO_L40N_GCLK10_M1A6_1_J12") (pintype "bidirectional"))
    )
    (net (code "33") (name "FPGA_J13") (class "Default")
      (node (ref "J1") (pin "38") (pinfunction "38_38") (pintype "passive"))
      (node (ref "U2") (pin "J13") (pinfunction "IO_L41P_GCLK9_IRDY1_M1RASN_1_J13") (pintype "bidirectional"))
    )
    (net (code "34") (name "FPGA_J14") (class "Default")
      (node (ref "J1") (pin "23") (pinfunction "23_23") (pintype "passive"))
      (node (ref "U2") (pin "J14") (pinfunction "IO_L43P_GCLK5_M1DQ4_1_J14") (pintype "bidirectional"))
    )
    (net (code "35") (name "FPGA_J16") (class "Default")
      (node (ref "J1") (pin "25") (pinfunction "25_25") (pintype "passive"))
      (node (ref "U2") (pin "J16") (pinfunction "IO_L43N_GCLK4_M1DQ5_1_J16") (pintype "bidirectional"))
    )
    (net (code "36") (name "FPGA_K11") (class "Default")
      (node (ref "J1") (pin "30") (pinfunction "30_30") (pintype "passive"))
      (node (ref "U2") (pin "K11") (pinfunction "IO_L42N_GCLK6_TRDY1_M1LDM_1_K11") (pintype "bidirectional"))
    )
    (net (code "37") (name "FPGA_K12") (class "Default")
      (node (ref "J1") (pin "32") (pinfunction "32_32") (pintype "passive"))
      (node (ref "U2") (pin "K12") (pinfunction "IO_L42P_GCLK7_M1UDM_1_K12") (pintype "bidirectional"))
    )
    (net (code "38") (name "FPGA_K14") (class "Default")
      (node (ref "J1") (pin "36") (pinfunction "36_36") (pintype "passive"))
      (node (ref "U2") (pin "K14") (pinfunction "IO_L41N_GCLK8_M1CASN_1_K14") (pintype "bidirectional"))
    )
    (net (code "39") (name "FPGA_K15") (class "Default")
      (node (ref "J1") (pin "31") (pinfunction "31_31") (pintype "passive"))
      (node (ref "U2") (pin "K15") (pinfunction "IO_L44P_A3_M1DQ6_1_K15") (pintype "bidirectional"))
    )
    (net (code "40") (name "FPGA_K16") (class "Default")
      (node (ref "J1") (pin "29") (pinfunction "29_29") (pintype "passive"))
      (node (ref "U2") (pin "K16") (pinfunction "IO_L44N_A2_M1DQ7_1_K16") (pintype "bidirectional"))
    )
    (net (code "41") (name "FPGA_L10") (class "Default")
      (node (ref "J1") (pin "13") (pinfunction "13_13") (pintype "passive"))
      (node (ref "U2") (pin "L10") (pinfunction "IO_L16P_2_L10") (pintype "bidirectional"))
    )
    (net (code "42") (name "FPGA_L12") (class "Default")
      (node (ref "J1") (pin "24") (pinfunction "24_24") (pintype "passive"))
      (node (ref "U2") (pin "L12") (pinfunction "IO_L53P_1_L12") (pintype "bidirectional"))
    )
    (net (code "43") (name "FPGA_L13") (class "Default")
      (node (ref "J1") (pin "26") (pinfunction "26_26") (pintype "passive"))
      (node (ref "U2") (pin "L13") (pinfunction "IO_L53N_VREF_1_L13") (pintype "bidirectional"))
    )
    (net (code "44") (name "FPGA_M10") (class "Default")
      (node (ref "J1") (pin "14") (pinfunction "14_14") (pintype "passive"))
      (node (ref "U2") (pin "M10") (pinfunction "IO_L16N_VREF_2_M10") (pintype "bidirectional"))
    )
    (net (code "45") (name "FPGA_M13") (class "Default")
      (node (ref "J1") (pin "18") (pinfunction "18_18") (pintype "passive"))
      (node (ref "U2") (pin "M13") (pinfunction "IO_L74P_AWAKE_1_M13") (pintype "bidirectional"))
    )
    (net (code "46") (name "FPGA_M14") (class "Default")
      (node (ref "J1") (pin "20") (pinfunction "20_20") (pintype "passive"))
      (node (ref "U2") (pin "M14") (pinfunction "IO_L74N_DOUT_BUSY_1_M14") (pintype "bidirectional"))
    )
    (net (code "47") (name "FPGA_N9") (class "Default")
      (node (ref "J1") (pin "12") (pinfunction "12_12") (pintype "passive"))
      (node (ref "U2") (pin "N9") (pinfunction "IO_L14P_D11_2_N9") (pintype "bidirectional"))
    )
    (net (code "48") (name "FPGA_P9") (class "Default")
      (node (ref "J1") (pin "10") (pinfunction "10_10") (pintype "passive"))
      (node (ref "U2") (pin "P9") (pinfunction "IO_L14N_D12_2_P9") (pintype "bidirectional"))
    )
    (net (code "49") (name "FPGA_P15") (class "Default")
      (node (ref "J1") (pin "19") (pinfunction "19_19") (pintype "passive"))
      (node (ref "U2") (pin "P15") (pinfunction "IO_L48P_HDC_M1DQ8_1_P15") (pintype "bidirectional"))
    )
    (net (code "50") (name "FPGA_P16") (class "Default")
      (node (ref "J1") (pin "17") (pinfunction "17_17") (pintype "passive"))
      (node (ref "U2") (pin "P16") (pinfunction "IO_L48N_M1DQ9_1_P16") (pintype "bidirectional"))
    )
    (net (code "51") (name "FPGA_R9") (class "Default")
      (node (ref "J1") (pin "11") (pinfunction "11_11") (pintype "passive"))
      (node (ref "U2") (pin "R9") (pinfunction "IO_L23P_2_R9") (pintype "bidirectional"))
    )
    (net (code "52") (name "FPGA_T9") (class "Default")
      (node (ref "J1") (pin "9") (pinfunction "9_9") (pintype "passive"))
      (node (ref "U2") (pin "T9") (pinfunction "IO_L23N_2_T9") (pintype "bidirectional"))
    )
    (net (code "53") (name "FX3_?") (class "Default")
      (node (ref "J2") (pin "57") (pinfunction "57_57") (pintype "passive"))
      (node (ref "U2") (pin "R1") (pinfunction "IO_L32N_M3DQ15_3_R1") (pintype "bidirectional"))
    )
    (net (code "54") (name "FX3_CTL0") (class "Default")
      (node (ref "J2") (pin "30") (pinfunction "30_30") (pintype "passive"))
      (node (ref "U2") (pin "H5") (pinfunction "IO_L43N_GCLK22_IRDY2_M3CASN_3_H5") (pintype "bidirectional"))
    )
    (net (code "55") (name "FX3_CTL1") (class "Default")
      (node (ref "J2") (pin "23") (pinfunction "23_23") (pintype "passive"))
      (node (ref "U2") (pin "E2") (pinfunction "IO_L46P_M3CLK_3_E2") (pintype "bidirectional"))
    )
    (net (code "56") (name "FX3_CTL2") (class "Default")
      (node (ref "J2") (pin "34") (pinfunction "34_34") (pintype "passive"))
      (node (ref "U2") (pin "H4") (pinfunction "IO_L44P_GCLK21_M3A5_3_H4") (pintype "bidirectional"))
    )
    (net (code "57") (name "FX3_CTL3") (class "Default")
      (node (ref "J2") (pin "36") (pinfunction "36_36") (pintype "passive"))
      (node (ref "U2") (pin "H3") (pinfunction "IO_L44N_GCLK20_M3A6_3_H3") (pintype "bidirectional"))
    )
    (net (code "58") (name "FX3_D0") (class "Default")
      (node (ref "J2") (pin "4") (pinfunction "4_4") (pintype "passive"))
      (node (ref "U2") (pin "A3") (pinfunction "IO_L83N_VREF_3_A3") (pintype "bidirectional"))
    )
    (net (code "59") (name "FX3_D1") (class "Default")
      (node (ref "J2") (pin "6") (pinfunction "6_6") (pintype "passive"))
      (node (ref "U2") (pin "B3") (pinfunction "IO_L83P_3_B3") (pintype "bidirectional"))
    )
    (net (code "60") (name "FX3_D2") (class "Default")
      (node (ref "J2") (pin "18") (pinfunction "18_18") (pintype "passive"))
      (node (ref "U2") (pin "E3") (pinfunction "IO_L54N_M3A11_3_E3") (pintype "bidirectional"))
    )
    (net (code "61") (name "FX3_D3") (class "Default")
      (node (ref "J2") (pin "12") (pinfunction "12_12") (pintype "passive"))
      (node (ref "U2") (pin "F5") (pinfunction "IO_L55N_M3A14_3_F5") (pintype "bidirectional"))
    )
    (net (code "62") (name "FX3_D4") (class "Default")
      (node (ref "J2") (pin "9") (pinfunction "9_9") (pintype "passive"))
      (node (ref "U2") (pin "B1") (pinfunction "IO_L50N_M3BA2_3_B1") (pintype "bidirectional"))
    )
    (net (code "63") (name "FX3_D5") (class "Default")
      (node (ref "J2") (pin "10") (pinfunction "10_10") (pintype "passive"))
      (node (ref "U2") (pin "F6") (pinfunction "IO_L55P_M3A13_3_F6") (pintype "bidirectional"))
    )
    (net (code "64") (name "FX3_D6") (class "Default")
      (node (ref "J2") (pin "5") (pinfunction "5_5") (pintype "passive"))
      (node (ref "U2") (pin "B2") (pinfunction "IO_L52P_M3A8_3_B2") (pintype "bidirectional"))
    )
    (net (code "65") (name "FX3_D7") (class "Default")
      (node (ref "J2") (pin "22") (pinfunction "22_22") (pintype "passive"))
      (node (ref "U2") (pin "G6") (pinfunction "IO_L51P_M3A10_3_G6") (pintype "bidirectional"))
    )
    (net (code "66") (name "FX3_D8") (class "Default")
      (node (ref "J2") (pin "16") (pinfunction "16_16") (pintype "passive"))
      (node (ref "U2") (pin "E4") (pinfunction "IO_L54P_M3RESET_3_E4") (pintype "bidirectional"))
    )
    (net (code "67") (name "FX3_D9") (class "Default")
      (node (ref "J2") (pin "15") (pinfunction "15_15") (pintype "passive"))
      (node (ref "U2") (pin "D1") (pinfunction "IO_L49N_M3A2_3_D1") (pintype "bidirectional"))
    )
    (net (code "68") (name "FX3_D10") (class "Default")
      (node (ref "J2") (pin "3") (pinfunction "3_3") (pintype "passive"))
      (node (ref "U2") (pin "A2") (pinfunction "IO_L52N_M3A9_3_A2") (pintype "bidirectional"))
    )
    (net (code "69") (name "FX3_D11") (class "Default")
      (node (ref "J2") (pin "24") (pinfunction "24_24") (pintype "passive"))
      (node (ref "U2") (pin "G5") (pinfunction "IO_L51N_M3A4_3_G5") (pintype "bidirectional"))
    )
    (net (code "70") (name "FX3_D12") (class "Default")
      (node (ref "J2") (pin "11") (pinfunction "11_11") (pintype "passive"))
      (node (ref "U2") (pin "C1") (pinfunction "IO_L50P_M3WE_3_C1") (pintype "bidirectional"))
    )
    (net (code "71") (name "FX3_D13") (class "Default")
      (node (ref "J2") (pin "17") (pinfunction "17_17") (pintype "passive"))
      (node (ref "U2") (pin "D3") (pinfunction "IO_L49P_M3A7_3_D3") (pintype "bidirectional"))
    )
    (net (code "72") (name "FX3_D14") (class "Default")
      (node (ref "J2") (pin "21") (pinfunction "21_21") (pintype "passive"))
      (node (ref "U2") (pin "E1") (pinfunction "IO_L46N_M3CLKN_3_E1") (pintype "bidirectional"))
    )
    (net (code "73") (name "FX3_D15") (class "Default")
      (node (ref "J2") (pin "28") (pinfunction "28_28") (pintype "passive"))
      (node (ref "U2") (pin "J6") (pinfunction "IO_L43P_GCLK23_M3RASN_3_J6") (pintype "bidirectional"))
    )
    (net (code "74") (name "FX3_D16") (class "Default")
      (node (ref "J2") (pin "35") (pinfunction "35_35") (pintype "passive"))
      (node (ref "U2") (pin "J4") (pinfunction "IO_L42N_GCLK24_M3LDM_3_J4") (pintype "bidirectional"))
    )
    (net (code "75") (name "FX3_D17") (class "Default")
      (node (ref "J2") (pin "40") (pinfunction "40_40") (pintype "passive"))
      (node (ref "U2") (pin "L5") (pinfunction "IO_L45N_M3ODT_3_L5") (pintype "bidirectional"))
    )
    (net (code "76") (name "FX3_D18") (class "Default")
      (node (ref "J2") (pin "54") (pinfunction "54_54") (pintype "passive"))
      (node (ref "U2") (pin "N4") (pinfunction "IO_L2N_3_N4") (pintype "bidirectional"))
    )
    (net (code "77") (name "FX3_D19") (class "Default")
      (node (ref "J2") (pin "41") (pinfunction "41_41") (pintype "passive"))
      (node (ref "U2") (pin "K1") (pinfunction "IO_L37N_M3DQ1_3_K1") (pintype "bidirectional"))
    )
    (net (code "78") (name "FX3_D20") (class "Default")
      (node (ref "J2") (pin "48") (pinfunction "48_48") (pintype "passive"))
      (node (ref "U2") (pin "M3") (pinfunction "IO_L1N_VREF_3_M3") (pintype "bidirectional"))
    )
    (net (code "79") (name "FX3_D21") (class "Default")
      (node (ref "J2") (pin "47") (pinfunction "47_47") (pintype "passive"))
      (node (ref "U2") (pin "M1") (pinfunction "IO_L35N_M3DQ11_3_M1") (pintype "bidirectional"))
    )
    (net (code "80") (name "FX3_D22") (class "Default")
      (node (ref "J2") (pin "45") (pinfunction "45_45") (pintype "passive"))
      (node (ref "U2") (pin "M2") (pinfunction "IO_L35P_M3DQ10_3_M2") (pintype "bidirectional"))
    )
    (net (code "81") (name "FX3_D23") (class "Default")
      (node (ref "J2") (pin "39") (pinfunction "39_39") (pintype "passive"))
      (node (ref "U2") (pin "K2") (pinfunction "IO_L37P_M3DQ0_3_K2") (pintype "bidirectional"))
    )
    (net (code "82") (name "FX3_D24") (class "Default")
      (node (ref "J2") (pin "33") (pinfunction "33_33") (pintype "passive"))
      (node (ref "U2") (pin "K3") (pinfunction "IO_L42P_GCLK25_TRDY2_M3UDM_3_K3") (pintype "bidirectional"))
    )
    (net (code "83") (name "FX3_D25") (class "Default")
      (node (ref "J2") (pin "58") (pinfunction "58_58") (pintype "passive"))
      (node (ref "U2") (pin "R2") (pinfunction "IO_L32P_M3DQ14_3_R2") (pintype "bidirectional"))
    )
    (net (code "84") (name "FX3_D26") (class "Default")
      (node (ref "J2") (pin "52") (pinfunction "52_52") (pintype "passive"))
      (node (ref "U2") (pin "M5") (pinfunction "IO_L2P_3_M5") (pintype "bidirectional"))
    )
    (net (code "85") (name "FX3_D27") (class "Default")
      (node (ref "J2") (pin "51") (pinfunction "51_51") (pintype "passive"))
      (node (ref "U2") (pin "P2") (pinfunction "IO_L33P_M3DQ12_3_P2") (pintype "bidirectional"))
    )
    (net (code "86") (name "FX3_D28") (class "Default")
      (node (ref "J2") (pin "53") (pinfunction "53_53") (pintype "passive"))
      (node (ref "U2") (pin "P1") (pinfunction "IO_L33N_M3DQ13_3_P1") (pintype "bidirectional"))
    )
    (net (code "87") (name "FX3_D29") (class "Default")
      (node (ref "J2") (pin "27") (pinfunction "27_27") (pintype "passive"))
      (node (ref "U2") (pin "F1") (pinfunction "IO_L41N_GCLK26_M3DQ5_3_F1") (pintype "bidirectional"))
    )
    (net (code "88") (name "FX3_D30") (class "Default")
      (node (ref "J2") (pin "42") (pinfunction "42_42") (pintype "passive"))
      (node (ref "U2") (pin "L4") (pinfunction "IO_L45P_M3A3_3_L4") (pintype "bidirectional"))
    )
    (net (code "89") (name "FX3_D31") (class "Default")
      (node (ref "J2") (pin "46") (pinfunction "46_46") (pintype "passive"))
      (node (ref "U2") (pin "M4") (pinfunction "IO_L1P_3_M4") (pintype "bidirectional"))
    )
    (net (code "90") (name "FX3_PCLK") (class "Default")
      (node (ref "J2") (pin "29") (pinfunction "29_29") (pintype "passive"))
      (node (ref "U2") (pin "F2") (pinfunction "IO_L41P_GCLK27_M3DQ4_3_F2") (pintype "bidirectional"))
    )
    (net (code "91") (name "GND") (class "Default")
      (node (ref "C1") (pin "1") (pinfunction "1_1") (pintype "passive"))
      (node (ref "C10") (pin "1") (pinfunction "1_1") (pintype "passive"))
      (node (ref "C11") (pin "1") (pinfunction "1_1") (pintype "passive"))
      (node (ref "C12") (pin "2") (pinfunction "2_2") (pintype "passive"))
      (node (ref "C13") (pin "1") (pinfunction "1_1") (pintype "passive"))
      (node (ref "C14") (pin "1") (pinfunction "1_1") (pintype "passive"))
      (node (ref "C15") (pin "1") (pinfunction "1_1") (pintype "passive"))
      (node (ref "C16") (pin "1") (pinfunction "1_1") (pintype "passive"))
      (node (ref "C17") (pin "2") (pinfunction "2_2") (pintype "passive"))
      (node (ref "C18") (pin "1") (pinfunction "1_1") (pintype "passive"))
      (node (ref "C19") (pin "1") (pinfunction "1_1") (pintype "passive"))
      (node (ref "C2") (pin "2") (pinfunction "2_2") (pintype "passive"))
      (node (ref "C20") (pin "1") (pinfunction "1_1") (pintype "passive"))
      (node (ref "C21") (pin "1") (pinfunction "1_1") (pintype "passive"))
      (node (ref "C22") (pin "1") (pinfunction "1_1") (pintype "passive"))
      (node (ref "C23") (pin "2") (pinfunction "2_2") (pintype "passive"))
      (node (ref "C24") (pin "1") (pinfunction "1_1") (pintype "passive"))
      (node (ref "C25") (pin "1") (pinfunction "1_1") (pintype "passive"))
      (node (ref "C26") (pin "1") (pinfunction "1_1") (pintype "passive"))
      (node (ref "C27") (pin "1") (pinfunction "1_1") (pintype "passive"))
      (node (ref "C28") (pin "1") (pinfunction "1_1") (pintype "passive"))
      (node (ref "C29") (pin "1") (pinfunction "1_1") (pintype "passive"))
      (node (ref "C3") (pin "2") (pinfunction "2_2") (pintype "passive"))
      (node (ref "C30") (pin "2") (pinfunction "2_2") (pintype "passive"))
      (node (ref "C31") (pin "1") (pinfunction "1_1") (pintype "passive"))
      (node (ref "C32") (pin "1") (pinfunction "1_1") (pintype "passive"))
      (node (ref "C33") (pin "1") (pinfunction "1_1") (pintype "passive"))
      (node (ref "C34") (pin "1") (pinfunction "1_1") (pintype "passive"))
      (node (ref "C35") (pin "1") (pinfunction "1_1") (pintype "passive"))
      (node (ref "C36") (pin "2") (pinfunction "2_2") (pintype "passive"))
      (node (ref "C4") (pin "1") (pinfunction "1_1") (pintype "passive"))
      (node (ref "C5") (pin "2") (pinfunction "2_2") (pintype "passive"))
      (node (ref "C6") (pin "2") (pinfunction "2_2") (pintype "passive"))
      (node (ref "C7") (pin "2") (pinfunction "2_2") (pintype "passive"))
      (node (ref "C8") (pin "1") (pinfunction "1_1") (pintype "passive"))
      (node (ref "C9") (pin "1") (pinfunction "1_1") (pintype "passive"))
      (node (ref "GND") (pin "TP") (pinfunction "TP_TP") (pintype "input"))
      (node (ref "J1") (pin "15") (pinfunction "15_15") (pintype "passive"))
      (node (ref "J1") (pin "16") (pinfunction "16_16") (pintype "passive"))
      (node (ref "J1") (pin "21") (pinfunction "21_21") (pintype "passive"))
      (node (ref "J1") (pin "22") (pinfunction "22_22") (pintype "passive"))
      (node (ref "J1") (pin "27") (pinfunction "27_27") (pintype "passive"))
      (node (ref "J1") (pin "28") (pinfunction "28_28") (pintype "passive"))
      (node (ref "J1") (pin "33") (pinfunction "33_33") (pintype "passive"))
      (node (ref "J1") (pin "34") (pinfunction "34_34") (pintype "passive"))
      (node (ref "J1") (pin "39") (pinfunction "39_39") (pintype "passive"))
      (node (ref "J1") (pin "40") (pinfunction "40_40") (pintype "passive"))
      (node (ref "J1") (pin "45") (pinfunction "45_45") (pintype "passive"))
      (node (ref "J1") (pin "46") (pinfunction "46_46") (pintype "passive"))
      (node (ref "J1") (pin "51") (pinfunction "51_51") (pintype "passive"))
      (node (ref "J1") (pin "52") (pinfunction "52_52") (pintype "passive"))
      (node (ref "J1") (pin "57") (pinfunction "57_57") (pintype "passive"))
      (node (ref "J1") (pin "58") (pinfunction "58_58") (pintype "passive"))
      (node (ref "J1") (pin "63") (pinfunction "63_63") (pintype "passive"))
      (node (ref "J1") (pin "64") (pinfunction "64_64") (pintype "passive"))
      (node (ref "J1") (pin "69") (pinfunction "69_69") (pintype "passive"))
      (node (ref "J1") (pin "7") (pinfunction "7_7") (pintype "passive"))
      (node (ref "J1") (pin "70") (pinfunction "70_70") (pintype "passive"))
      (node (ref "J1") (pin "8") (pinfunction "8_8") (pintype "passive"))
      (node (ref "J1") (pin "S1") (pinfunction "SHIELD_S1") (pintype "passive"))
      (node (ref "J1") (pin "S2") (pinfunction "SHIELD_S2") (pintype "passive"))
      (node (ref "J2") (pin "1") (pinfunction "1_1") (pintype "passive"))
      (node (ref "J2") (pin "13") (pinfunction "13_13") (pintype "passive"))
      (node (ref "J2") (pin "14") (pinfunction "14_14") (pintype "passive"))
      (node (ref "J2") (pin "19") (pinfunction "19_19") (pintype "passive"))
      (node (ref "J2") (pin "2") (pinfunction "2_2") (pintype "passive"))
      (node (ref "J2") (pin "20") (pinfunction "20_20") (pintype "passive"))
      (node (ref "J2") (pin "25") (pinfunction "25_25") (pintype "passive"))
      (node (ref "J2") (pin "26") (pinfunction "26_26") (pintype "passive"))
      (node (ref "J2") (pin "31") (pinfunction "31_31") (pintype "passive"))
      (node (ref "J2") (pin "32") (pinfunction "32_32") (pintype "passive"))
      (node (ref "J2") (pin "37") (pinfunction "37_37") (pintype "passive"))
      (node (ref "J2") (pin "38") (pinfunction "38_38") (pintype "passive"))
      (node (ref "J2") (pin "43") (pinfunction "43_43") (pintype "passive"))
      (node (ref "J2") (pin "44") (pinfunction "44_44") (pintype "passive"))
      (node (ref "J2") (pin "49") (pinfunction "49_49") (pintype "passive"))
      (node (ref "J2") (pin "50") (pinfunction "50_50") (pintype "passive"))
      (node (ref "J2") (pin "55") (pinfunction "55_55") (pintype "passive"))
      (node (ref "J2") (pin "56") (pinfunction "56_56") (pintype "passive"))
      (node (ref "J2") (pin "59") (pinfunction "59_59") (pintype "passive"))
      (node (ref "J2") (pin "60") (pinfunction "60_60") (pintype "passive"))
      (node (ref "J2") (pin "7") (pinfunction "7_7") (pintype "passive"))
      (node (ref "J2") (pin "8") (pinfunction "8_8") (pintype "passive"))
      (node (ref "J2") (pin "S1") (pinfunction "SHIELD_S1") (pintype "passive"))
      (node (ref "J2") (pin "S2") (pinfunction "SHIELD_S2") (pintype "passive"))
      (node (ref "JTAG") (pin "2") (pinfunction "2_2") (pintype "passive"))
      (node (ref "R10") (pin "2") (pinfunction "2_2") (pintype "passive"))
      (node (ref "R13") (pin "1") (pinfunction "1_1") (pintype "passive"))
      (node (ref "R15") (pin "1") (pinfunction "1_1") (pintype "passive"))
      (node (ref "R19") (pin "1") (pinfunction "1_1") (pintype "passive"))
      (node (ref "R22") (pin "1") (pinfunction "1_1") (pintype "passive"))
      (node (ref "R9") (pin "2") (pinfunction "2_2") (pintype "passive"))
      (node (ref "U1") (pin "2") (pinfunction "GND_2") (pintype "passive"))
      (node (ref "U2") (pin "A1") (pinfunction "GND_A1") (pintype "power_in"))
      (node (ref "U2") (pin "A16") (pinfunction "GND_A16") (pintype "power_in"))
      (node (ref "U2") (pin "B11") (pinfunction "GND_B11") (pintype "power_in"))
      (node (ref "U2") (pin "B7") (pinfunction "GND_B7") (pintype "power_in"))
      (node (ref "U2") (pin "D13") (pinfunction "GND_D13") (pintype "power_in"))
      (node (ref "U2") (pin "D4") (pinfunction "GND_D4") (pintype "power_in"))
      (node (ref "U2") (pin "E9") (pinfunction "GND_E9") (pintype "power_in"))
      (node (ref "U2") (pin "G15") (pinfunction "GND_G15") (pintype "power_in"))
      (node (ref "U2") (pin "G2") (pinfunction "GND_G2") (pintype "power_in"))
      (node (ref "U2") (pin "G8") (pinfunction "GND_G8") (pintype "power_in"))
      (node (ref "U2") (pin "H12") (pinfunction "GND_H12") (pintype "power_in"))
      (node (ref "U2") (pin "H7") (pinfunction "GND_H7") (pintype "power_in"))
      (node (ref "U2") (pin "H9") (pinfunction "GND_H9") (pintype "power_in"))
      (node (ref "U2") (pin "J5") (pinfunction "GND_J5") (pintype "power_in"))
      (node (ref "U2") (pin "J8") (pinfunction "GND_J8") (pintype "power_in"))
      (node (ref "U2") (pin "K7") (pinfunction "GND_K7") (pintype "power_in"))
      (node (ref "U2") (pin "K9") (pinfunction "GND_K9") (pintype "power_in"))
      (node (ref "U2") (pin "L15") (pinfunction "GND_L15") (pintype "power_in"))
      (node (ref "U2") (pin "L2") (pinfunction "GND_L2") (pintype "power_in"))
      (node (ref "U2") (pin "M8") (pinfunction "GND_M8") (pintype "power_in"))
      (node (ref "U2") (pin "N13") (pinfunction "GND_N13") (pintype "power_in"))
      (node (ref "U2") (pin "P14") (pinfunction "SUSPEND_P14") (pintype "input"))
      (node (ref "U2") (pin "P3") (pinfunction "GND_P3") (pintype "power_in"))
      (node (ref "U2") (pin "R10") (pinfunction "GND_R10") (pintype "power_in"))
      (node (ref "U2") (pin "R6") (pinfunction "GND_R6") (pintype "power_in"))
      (node (ref "U2") (pin "T1") (pinfunction "GND_T1") (pintype "power_in"))
      (node (ref "U2") (pin "T16") (pinfunction "GND_T16") (pintype "power_in"))
      (node (ref "U3") (pin "4") (pinfunction "VSS_4") (pintype "bidirectional"))
      (node (ref "U3") (pin "EP") (pinfunction "EP_EP") (pintype "bidirectional"))
      (node (ref "U4") (pin "1") (pinfunction "GND_1") (pintype "bidirectional"))
      (node (ref "U5") (pin "1") (pinfunction "GND_1") (pintype "bidirectional"))
      (node (ref "U6") (pin "2") (pinfunction "GND_2") (pintype "power_in"))
      (node (ref "U7") (pin "1") (pinfunction "GND_1") (pintype "bidirectional"))
      (node (ref "X1") (pin "2") (pinfunction "GND_2") (pintype "power_in"))
    )
    (net (code "92") (name "HSWAPEN") (class "Default")
      (node (ref "R3") (pin "2") (pinfunction "2_2") (pintype "passive"))
      (node (ref "U2") (pin "C4") (pinfunction "IO_L1P_HSWAPEN_0_C4") (pintype "bidirectional"))
    )
    (net (code "93") (name "INIT") (class "Default")
      (node (ref "R1") (pin "1") (pinfunction "1_1") (pintype "passive"))
      (node (ref "U2") (pin "R3") (pinfunction "IO_L65P_INIT_B_2_R3") (pintype "bidirectional"))
    )
    (net (code "94") (name "LED") (class "Default")
      (node (ref "LED") (pin "A") (pinfunction "A_A") (pintype "passive"))
      (node (ref "U2") (pin "A13") (pinfunction "IO_L63N_SCP6_0_A13") (pintype "bidirectional"))
    )
    (net (code "95") (name "M0_0") (class "Default")
      (node (ref "R11") (pin "2") (pinfunction "2_2") (pintype "passive"))
      (node (ref "U2") (pin "T11") (pinfunction "IO_L1N_M0_CMPMISO_2_T11") (pintype "bidirectional"))
    )
    (net (code "96") (name "M1_0") (class "Default")
      (node (ref "R10") (pin "1") (pinfunction "1_1") (pintype "passive"))
      (node (ref "U2") (pin "N11") (pinfunction "IO_L13P_M1_2_N11") (pintype "bidirectional"))
    )
    (net (code "97") (name "Net-(DONE-PadC)") (class "Default")
      (node (ref "DONE") (pin "C") (pinfunction "C_C") (pintype "passive"))
      (node (ref "R23") (pin "2") (pinfunction "2_2") (pintype "passive"))
    )
    (net (code "98") (name "Net-(JTAG-Pad3)") (class "Default")
      (node (ref "JTAG") (pin "3") (pinfunction "3_3") (pintype "passive"))
      (node (ref "R20") (pin "1") (pinfunction "1_1") (pintype "passive"))
    )
    (net (code "99") (name "Net-(JTAG-Pad5)") (class "Default")
      (node (ref "JTAG") (pin "5") (pinfunction "5_5") (pintype "passive"))
      (node (ref "R17") (pin "1") (pinfunction "1_1") (pintype "passive"))
    )
    (net (code "100") (name "Net-(JTAG-Pad6)") (class "Default")
      (node (ref "JTAG") (pin "6") (pinfunction "6_6") (pintype "passive"))
      (node (ref "R16") (pin "1") (pinfunction "1_1") (pintype "passive"))
    )
    (net (code "101") (name "Net-(LED-PadC)") (class "Default")
      (node (ref "LED") (pin "C") (pinfunction "C_C") (pintype "passive"))
      (node (ref "R13") (pin "2") (pinfunction "2_2") (pintype "passive"))
    )
    (net (code "102") (name "Net-(U2A-IO_L34N_GCLK18_0)") (class "Default")
      (node (ref "A9") (pin "TP") (pinfunction "TP_TP") (pintype "input"))
      (node (ref "U2") (pin "A9") (pinfunction "IO_L34N_GCLK18_0_A9") (pintype "bidirectional"))
    )
    (net (code "103") (name "Net-(U2A-IO_L34P_GCLK19_0)") (class "Default")
      (node (ref "CC9") (pin "TP") (pinfunction "TP_TP") (pintype "input"))
      (node (ref "U2") (pin "C9") (pinfunction "IO_L34P_GCLK19_0_C9") (pintype "bidirectional"))
    )
    (net (code "104") (name "Net-(U2A-IO_L35N_GCLK16_0)") (class "Default")
      (node (ref "AX") (pin "TP") (pinfunction "TP_TP") (pintype "input"))
      (node (ref "U2") (pin "A10") (pinfunction "IO_L35N_GCLK16_0_A10") (pintype "bidirectional"))
    )
    (net (code "105") (name "Net-(U2A-IO_L35P_GCLK17_0)") (class "Default")
      (node (ref "BX") (pin "TP") (pinfunction "TP_TP") (pintype "input"))
      (node (ref "U2") (pin "B10") (pinfunction "IO_L35P_GCLK17_0_B10") (pintype "bidirectional"))
    )
    (net (code "106") (name "Net-(U3-DQ1)") (class "Default")
      (node (ref "R4") (pin "1") (pinfunction "1_1") (pintype "passive"))
      (node (ref "U3") (pin "2") (pinfunction "DQ1_2") (pintype "bidirectional"))
    )
    (net (code "107") (name "Net-(U4-FB)") (class "Default")
      (node (ref "R14") (pin "2") (pinfunction "2_2") (pintype "passive"))
      (node (ref "R15") (pin "2") (pinfunction "2_2") (pintype "passive"))
      (node (ref "U4") (pin "5") (pinfunction "FB_5") (pintype "bidirectional"))
    )
    (net (code "108") (name "Net-(U4-SW)") (class "Default")
      (node (ref "L1") (pin "2") (pinfunction "2_2") (pintype "passive"))
      (node (ref "U4") (pin "2") (pinfunction "SW_2") (pintype "bidirectional"))
    )
    (net (code "109") (name "Net-(U5-FB)") (class "Default")
      (node (ref "R18") (pin "2") (pinfunction "2_2") (pintype "passive"))
      (node (ref "R19") (pin "2") (pinfunction "2_2") (pintype "passive"))
      (node (ref "U5") (pin "5") (pinfunction "FB_5") (pintype "bidirectional"))
    )
    (net (code "110") (name "Net-(U5-SW)") (class "Default")
      (node (ref "L2") (pin "2") (pinfunction "2_2") (pintype "passive"))
      (node (ref "U5") (pin "2") (pinfunction "SW_2") (pintype "bidirectional"))
    )
    (net (code "111") (name "Net-(U7-FB)") (class "Default")
      (node (ref "R21") (pin "2") (pinfunction "2_2") (pintype "passive"))
      (node (ref "R22") (pin "2") (pinfunction "2_2") (pintype "passive"))
      (node (ref "U7") (pin "5") (pinfunction "FB_5") (pintype "bidirectional"))
    )
    (net (code "112") (name "Net-(U7-SW)") (class "Default")
      (node (ref "L3") (pin "2") (pinfunction "2_2") (pintype "passive"))
      (node (ref "U7") (pin "2") (pinfunction "SW_2") (pintype "bidirectional"))
    )
    (net (code "113") (name "PROG") (class "Default")
      (node (ref "R2") (pin "2") (pinfunction "2_2") (pintype "passive"))
      (node (ref "U2") (pin "T2") (pinfunction "PROGRAM_B_2_T2") (pintype "input"))
    )
    (net (code "114") (name "PROG_DONE") (class "Default")
      (node (ref "R23") (pin "1") (pinfunction "1_1") (pintype "passive"))
      (node (ref "R24") (pin "1") (pinfunction "1_1") (pintype "passive"))
      (node (ref "U2") (pin "P13") (pinfunction "DONE_2_P13") (pintype "bidirectional"))
    )
    (net (code "115") (name "SCL") (class "Default")
      (node (ref "R6") (pin "2") (pinfunction "2_2") (pintype "passive"))
      (node (ref "U1") (pin "4") (pinfunction "SCL_4") (pintype "input"))
      (node (ref "U2") (pin "A5") (pinfunction "IO_L2N_0_A5") (pintype "bidirectional"))
      (node (ref "U6") (pin "1") (pinfunction "SCL_1") (pintype "input"))
    )
    (net (code "116") (name "SDA") (class "Default")
      (node (ref "R7") (pin "2") (pinfunction "2_2") (pintype "passive"))
      (node (ref "U1") (pin "5") (pinfunction "SDA_5") (pintype "bidirectional"))
      (node (ref "U2") (pin "A4") (pinfunction "IO_L1N_VREF_0_A4") (pintype "bidirectional"))
      (node (ref "U6") (pin "3") (pinfunction "SDA_3") (pintype "bidirectional"))
    )
    (net (code "117") (name "TCK") (class "Default")
      (node (ref "R20") (pin "2") (pinfunction "2_2") (pintype "passive"))
      (node (ref "U2") (pin "C14") (pinfunction "TCK_C14") (pintype "input"))
    )
    (net (code "118") (name "TDI") (class "Default")
      (node (ref "R17") (pin "2") (pinfunction "2_2") (pintype "passive"))
      (node (ref "U2") (pin "C12") (pinfunction "TDI_C12") (pintype "input"))
    )
    (net (code "119") (name "TDO") (class "Default")
      (node (ref "JTAG") (pin "4") (pinfunction "4_4") (pintype "passive"))
      (node (ref "U2") (pin "E14") (pinfunction "TDO_E14") (pintype "output"))
    )
    (net (code "120") (name "TMS") (class "Default")
      (node (ref "R16") (pin "2") (pinfunction "2_2") (pintype "passive"))
      (node (ref "U2") (pin "A15") (pinfunction "TMS_A15") (pintype "input"))
    )
    (net (code "121") (name "UART_CTS") (class "Default")
      (node (ref "J2") (pin "63") (pinfunction "63_63") (pintype "passive"))
      (node (ref "U2") (pin "T6") (pinfunction "IO_L47N_2_T6") (pintype "bidirectional"))
    )
    (net (code "122") (name "UART_RTS") (class "Default")
      (node (ref "J2") (pin "61") (pinfunction "61_61") (pintype "passive"))
      (node (ref "U2") (pin "P6") (pinfunction "IO_L47P_2_P6") (pintype "bidirectional"))
    )
    (net (code "123") (name "UART_RX") (class "Default")
      (node (ref "J2") (pin "62") (pinfunction "62_62") (pintype "passive"))
      (node (ref "U2") (pin "R5") (pinfunction "IO_L48P_D7_2_R5") (pintype "bidirectional"))
    )
    (net (code "124") (name "UART_TX") (class "Default")
      (node (ref "J2") (pin "64") (pinfunction "64_64") (pintype "passive"))
      (node (ref "U2") (pin "T5") (pinfunction "IO_L48N_RDWR_B_VREF_2_T5") (pintype "bidirectional"))
    )
    (net (code "125") (name "VIO_B1") (class "Default")
      (node (ref "B1") (pin "2") (pinfunction "2_2") (pintype "passive"))
      (node (ref "C10") (pin "2") (pinfunction "2_2") (pintype "passive"))
      (node (ref "C11") (pin "2") (pinfunction "2_2") (pintype "passive"))
      (node (ref "C8") (pin "2") (pinfunction "2_2") (pintype "passive"))
      (node (ref "C9") (pin "2") (pinfunction "2_2") (pintype "passive"))
      (node (ref "U2") (pin "D15") (pinfunction "VCCO_1_D15") (pintype "input"))
      (node (ref "U2") (pin "G13") (pinfunction "VCCO_1_G13") (pintype "input"))
      (node (ref "U2") (pin "J15") (pinfunction "VCCO_1_J15") (pintype "input"))
      (node (ref "U2") (pin "K13") (pinfunction "VCCO_1_K13") (pintype "input"))
      (node (ref "U2") (pin "N15") (pinfunction "VCCO_1_N15") (pintype "input"))
      (node (ref "U2") (pin "R13") (pinfunction "VCCO_1_R13") (pintype "input"))
    )
    (net (code "126") (name "unconnected-(U1-ALERT-Pad3)") (class "Default")
      (node (ref "U1") (pin "3") (pinfunction "ALERT_3") (pintype "output"))
    )
    (net (code "127") (name "unconnected-(U2A-IO_L2P_0-PadB5)") (class "Default")
      (node (ref "U2") (pin "B5") (pinfunction "IO_L2P_0_B5") (pintype "bidirectional"))
    )
    (net (code "128") (name "unconnected-(U2A-IO_L3N_0-PadC5)") (class "Default")
      (node (ref "U2") (pin "C5") (pinfunction "IO_L3N_0_C5") (pintype "bidirectional"))
    )
    (net (code "129") (name "unconnected-(U2A-IO_L3P_0-PadD5)") (class "Default")
      (node (ref "U2") (pin "D5") (pinfunction "IO_L3P_0_D5") (pintype "bidirectional"))
    )
    (net (code "130") (name "unconnected-(U2A-IO_L4N_0-PadA6)") (class "Default")
      (node (ref "U2") (pin "A6") (pinfunction "IO_L4N_0_A6") (pintype "bidirectional"))
    )
    (net (code "131") (name "unconnected-(U2A-IO_L4P_0-PadB6)") (class "Default")
      (node (ref "U2") (pin "B6") (pinfunction "IO_L4P_0_B6") (pintype "bidirectional"))
    )
    (net (code "132") (name "unconnected-(U2A-IO_L5N_0-PadE6)") (class "Default")
      (node (ref "U2") (pin "E6") (pinfunction "IO_L5N_0_E6") (pintype "bidirectional"))
    )
    (net (code "133") (name "unconnected-(U2A-IO_L5P_0-PadF7)") (class "Default")
      (node (ref "U2") (pin "F7") (pinfunction "IO_L5P_0_F7") (pintype "bidirectional"))
    )
    (net (code "134") (name "unconnected-(U2A-IO_L6N_0-PadA7)") (class "Default")
      (node (ref "U2") (pin "A7") (pinfunction "IO_L6N_0_A7") (pintype "bidirectional"))
    )
    (net (code "135") (name "unconnected-(U2A-IO_L6P_0-PadC7)") (class "Default")
      (node (ref "U2") (pin "C7") (pinfunction "IO_L6P_0_C7") (pintype "bidirectional"))
    )
    (net (code "136") (name "unconnected-(U2A-IO_L7N_0-PadC6)") (class "Default")
      (node (ref "U2") (pin "C6") (pinfunction "IO_L7N_0_C6") (pintype "bidirectional"))
    )
    (net (code "137") (name "unconnected-(U2A-IO_L7P_0-PadD6)") (class "Default")
      (node (ref "U2") (pin "D6") (pinfunction "IO_L7P_0_D6") (pintype "bidirectional"))
    )
    (net (code "138") (name "unconnected-(U2A-IO_L33N_0-PadA8)") (class "Default")
      (node (ref "U2") (pin "A8") (pinfunction "IO_L33N_0_A8") (pintype "bidirectional"))
    )
    (net (code "139") (name "unconnected-(U2A-IO_L33P_0-PadB8)") (class "Default")
      (node (ref "U2") (pin "B8") (pinfunction "IO_L33P_0_B8") (pintype "bidirectional"))
    )
    (net (code "140") (name "unconnected-(U2A-IO_L36N_GCLK14_0-PadE8)") (class "Default")
      (node (ref "U2") (pin "E8") (pinfunction "IO_L36N_GCLK14_0_E8") (pintype "bidirectional"))
    )
    (net (code "141") (name "unconnected-(U2A-IO_L36P_GCLK15_0-PadE7)") (class "Default")
      (node (ref "U2") (pin "E7") (pinfunction "IO_L36P_GCLK15_0_E7") (pintype "bidirectional"))
    )
    (net (code "142") (name "unconnected-(U2A-IO_L37N_GCLK12_0-PadC10)") (class "Default")
      (node (ref "U2") (pin "C10") (pinfunction "IO_L37N_GCLK12_0_C10") (pintype "bidirectional"))
    )
    (net (code "143") (name "unconnected-(U2A-IO_L37P_GCLK13_0-PadE10)") (class "Default")
      (node (ref "U2") (pin "E10") (pinfunction "IO_L37P_GCLK13_0_E10") (pintype "bidirectional"))
    )
    (net (code "144") (name "unconnected-(U2A-IO_L38N_VREF_0-PadC8)") (class "Default")
      (node (ref "U2") (pin "C8") (pinfunction "IO_L38N_VREF_0_C8") (pintype "bidirectional"))
    )
    (net (code "145") (name "unconnected-(U2A-IO_L38P_0-PadD8)") (class "Default")
      (node (ref "U2") (pin "D8") (pinfunction "IO_L38P_0_D8") (pintype "bidirectional"))
    )
    (net (code "146") (name "unconnected-(U2A-IO_L39N_0-PadA11)") (class "Default")
      (node (ref "U2") (pin "A11") (pinfunction "IO_L39N_0_A11") (pintype "bidirectional"))
    )
    (net (code "147") (name "unconnected-(U2A-IO_L39P_0-PadC11)") (class "Default")
      (node (ref "U2") (pin "C11") (pinfunction "IO_L39P_0_C11") (pintype "bidirectional"))
    )
    (net (code "148") (name "unconnected-(U2A-IO_L40N_0-PadD9)") (class "Default")
      (node (ref "U2") (pin "D9") (pinfunction "IO_L40N_0_D9") (pintype "bidirectional"))
    )
    (net (code "149") (name "unconnected-(U2A-IO_L40P_0-PadF9)") (class "Default")
      (node (ref "U2") (pin "F9") (pinfunction "IO_L40P_0_F9") (pintype "bidirectional"))
    )
    (net (code "150") (name "unconnected-(U2A-IO_L62N_VREF_0-PadA12)") (class "Default")
      (node (ref "U2") (pin "A12") (pinfunction "IO_L62N_VREF_0_A12") (pintype "bidirectional"))
    )
    (net (code "151") (name "unconnected-(U2A-IO_L62P_0-PadB12)") (class "Default")
      (node (ref "U2") (pin "B12") (pinfunction "IO_L62P_0_B12") (pintype "bidirectional"))
    )
    (net (code "152") (name "unconnected-(U2A-IO_L63P_SCP7_0-PadC13)") (class "Default")
      (node (ref "U2") (pin "C13") (pinfunction "IO_L63P_SCP7_0_C13") (pintype "bidirectional"))
    )
    (net (code "153") (name "unconnected-(U2A-IO_L64N_SCP4_0-PadE11)") (class "Default")
      (node (ref "U2") (pin "E11") (pinfunction "IO_L64N_SCP4_0_E11") (pintype "bidirectional"))
    )
    (net (code "154") (name "unconnected-(U2A-IO_L64P_SCP5_0-PadF10)") (class "Default")
      (node (ref "U2") (pin "F10") (pinfunction "IO_L64P_SCP5_0_F10") (pintype "bidirectional"))
    )
    (net (code "155") (name "unconnected-(U2A-IO_L65N_SCP2_0-PadA14)") (class "Default")
      (node (ref "U2") (pin "A14") (pinfunction "IO_L65N_SCP2_0_A14") (pintype "bidirectional"))
    )
    (net (code "156") (name "unconnected-(U2A-IO_L65P_SCP3_0-PadB14)") (class "Default")
      (node (ref "U2") (pin "B14") (pinfunction "IO_L65P_SCP3_0_B14") (pintype "bidirectional"))
    )
    (net (code "157") (name "unconnected-(U2A-IO_L66N_SCP0_0-PadD12)") (class "Default")
      (node (ref "U2") (pin "D12") (pinfunction "IO_L66N_SCP0_0_D12") (pintype "bidirectional"))
    )
    (net (code "158") (name "unconnected-(U2A-IO_L66P_SCP1_0-PadD11)") (class "Default")
      (node (ref "U2") (pin "D11") (pinfunction "IO_L66P_SCP1_0_D11") (pintype "bidirectional"))
    )
    (net (code "159") (name "unconnected-(U2B-IO_L30N_A20_M1A11_1-PadG11)") (class "Default")
      (node (ref "U2") (pin "G11") (pinfunction "IO_L30N_A20_M1A11_1_G11") (pintype "bidirectional"))
    )
    (net (code "160") (name "unconnected-(U2B-IO_L30P_A21_M1RESET_1-PadF12)") (class "Default")
      (node (ref "U2") (pin "F12") (pinfunction "IO_L30P_A21_M1RESET_1_F12") (pintype "bidirectional"))
    )
    (net (code "161") (name "unconnected-(U2B-IO_L38N_A4_M1CLKN_1-PadH11)") (class "Default")
      (node (ref "U2") (pin "H11") (pinfunction "IO_L38N_A4_M1CLKN_1_H11") (pintype "bidirectional"))
    )
    (net (code "162") (name "unconnected-(U2B-IO_L38P_A5_M1CLK_1-PadG12)") (class "Default")
      (node (ref "U2") (pin "G12") (pinfunction "IO_L38P_A5_M1CLK_1_G12") (pintype "bidirectional"))
    )
    (net (code "163") (name "unconnected-(U2B-IO_L45N_A0_M1LDQSN_1-PadN16)") (class "Default")
      (node (ref "U2") (pin "N16") (pinfunction "IO_L45N_A0_M1LDQSN_1_N16") (pintype "bidirectional"))
    )
    (net (code "164") (name "unconnected-(U2B-IO_L45P_A1_M1LDQS_1-PadN14)") (class "Default")
      (node (ref "U2") (pin "N14") (pinfunction "IO_L45P_A1_M1LDQS_1_N14") (pintype "bidirectional"))
    )
    (net (code "165") (name "unconnected-(U2B-IO_L46N_FOE_B_M1DQ3_1-PadM16)") (class "Default")
      (node (ref "U2") (pin "M16") (pinfunction "IO_L46N_FOE_B_M1DQ3_1_M16") (pintype "bidirectional"))
    )
    (net (code "166") (name "unconnected-(U2B-IO_L46P_FCS_B_M1DQ2_1-PadM15)") (class "Default")
      (node (ref "U2") (pin "M15") (pinfunction "IO_L46P_FCS_B_M1DQ2_1_M15") (pintype "bidirectional"))
    )
    (net (code "167") (name "unconnected-(U2B-IO_L47N_LDC_M1DQ1_1-PadL16)") (class "Default")
      (node (ref "U2") (pin "L16") (pinfunction "IO_L47N_LDC_M1DQ1_1_L16") (pintype "bidirectional"))
    )
    (net (code "168") (name "unconnected-(U2B-IO_L47P_FWE_B_M1DQ0_1-PadL14)") (class "Default")
      (node (ref "U2") (pin "L14") (pinfunction "IO_L47P_FWE_B_M1DQ0_1_L14") (pintype "bidirectional"))
    )
    (net (code "169") (name "unconnected-(U2B-IO_L49N_M1DQ11_1-PadR16)") (class "Default")
      (node (ref "U2") (pin "R16") (pinfunction "IO_L49N_M1DQ11_1_R16") (pintype "bidirectional"))
    )
    (net (code "170") (name "unconnected-(U2B-IO_L49P_M1DQ10_1-PadR15)") (class "Default")
      (node (ref "U2") (pin "R15") (pinfunction "IO_L49P_M1DQ10_1_R15") (pintype "bidirectional"))
    )
    (net (code "171") (name "unconnected-(U2B-IO_L50N_M1UDQSN_1-PadT15)") (class "Default")
      (node (ref "U2") (pin "T15") (pinfunction "IO_L50N_M1UDQSN_1_T15") (pintype "bidirectional"))
    )
    (net (code "172") (name "unconnected-(U2B-IO_L50P_M1UDQS_1-PadR14)") (class "Default")
      (node (ref "U2") (pin "R14") (pinfunction "IO_L50P_M1UDQS_1_R14") (pintype "bidirectional"))
    )
    (net (code "173") (name "unconnected-(U2B-IO_L51N_M1DQ13_1-PadT13)") (class "Default")
      (node (ref "U2") (pin "T13") (pinfunction "IO_L51N_M1DQ13_1_T13") (pintype "bidirectional"))
    )
    (net (code "174") (name "unconnected-(U2B-IO_L51P_M1DQ12_1-PadT14)") (class "Default")
      (node (ref "U2") (pin "T14") (pinfunction "IO_L51P_M1DQ12_1_T14") (pintype "bidirectional"))
    )
    (net (code "175") (name "unconnected-(U2B-IO_L52N_M1DQ15_1-PadT12)") (class "Default")
      (node (ref "U2") (pin "T12") (pinfunction "IO_L52N_M1DQ15_1_T12") (pintype "bidirectional"))
    )
    (net (code "176") (name "unconnected-(U2B-IO_L52P_M1DQ14_1-PadR12)") (class "Default")
      (node (ref "U2") (pin "R12") (pinfunction "IO_L52P_M1DQ14_1_R12") (pintype "bidirectional"))
    )
    (net (code "177") (name "unconnected-(U2C-IO_L2N_CMPMOSI_2-PadM11)") (class "Default")
      (node (ref "U2") (pin "M11") (pinfunction "IO_L2N_CMPMOSI_2_M11") (pintype "bidirectional"))
    )
    (net (code "178") (name "unconnected-(U2C-IO_L2P_CMPCLK_2-PadM12)") (class "Default")
      (node (ref "U2") (pin "M12") (pinfunction "IO_L2P_CMPCLK_2_M12") (pintype "bidirectional"))
    )
    (net (code "179") (name "unconnected-(U2C-IO_L12N_D2_MISO3_2-PadP12)") (class "Default")
      (node (ref "U2") (pin "P12") (pinfunction "IO_L12N_D2_MISO3_2_P12") (pintype "bidirectional"))
    )
    (net (code "180") (name "unconnected-(U2C-IO_L12P_D1_MISO2_2-PadN12)") (class "Default")
      (node (ref "U2") (pin "N12") (pinfunction "IO_L12P_D1_MISO2_2_N12") (pintype "bidirectional"))
    )
    (net (code "181") (name "unconnected-(U2C-IO_L13N_D10_2-PadP11)") (class "Default")
      (node (ref "U2") (pin "P11") (pinfunction "IO_L13N_D10_2_P11") (pintype "bidirectional"))
    )
    (net (code "182") (name "unconnected-(U2C-IO_L29N_GCLK2_2-PadN8)") (class "Default")
      (node (ref "U2") (pin "N8") (pinfunction "IO_L29N_GCLK2_2_N8") (pintype "bidirectional"))
    )
    (net (code "183") (name "unconnected-(U2C-IO_L29P_GCLK3_2-PadM9)") (class "Default")
      (node (ref "U2") (pin "M9") (pinfunction "IO_L29P_GCLK3_2_M9") (pintype "bidirectional"))
    )
    (net (code "184") (name "unconnected-(U2C-IO_L30N_GCLK0_USERCCLK_2-PadT8)") (class "Default")
      (node (ref "U2") (pin "T8") (pinfunction "IO_L30N_GCLK0_USERCCLK_2_T8") (pintype "bidirectional"))
    )
    (net (code "185") (name "unconnected-(U2C-IO_L30P_GCLK1_D13_2-PadP8)") (class "Default")
      (node (ref "U2") (pin "P8") (pinfunction "IO_L30P_GCLK1_D13_2_P8") (pintype "bidirectional"))
    )
    (net (code "186") (name "unconnected-(U2C-IO_L31N_GCLK30_D15_2-PadM7)") (class "Default")
      (node (ref "U2") (pin "M7") (pinfunction "IO_L31N_GCLK30_D15_2_M7") (pintype "bidirectional"))
    )
    (net (code "187") (name "unconnected-(U2C-IO_L31P_GCLK31_D14_2-PadP7)") (class "Default")
      (node (ref "U2") (pin "P7") (pinfunction "IO_L31P_GCLK31_D14_2_P7") (pintype "bidirectional"))
    )
    (net (code "188") (name "unconnected-(U2C-IO_L32P_GCLK29_2-PadR7)") (class "Default")
      (node (ref "U2") (pin "R7") (pinfunction "IO_L32P_GCLK29_2_R7") (pintype "bidirectional"))
    )
    (net (code "189") (name "unconnected-(U2C-IO_L49N_D4_2-PadP5)") (class "Default")
      (node (ref "U2") (pin "P5") (pinfunction "IO_L49N_D4_2_P5") (pintype "bidirectional"))
    )
    (net (code "190") (name "unconnected-(U2C-IO_L49P_D3_2-PadN5)") (class "Default")
      (node (ref "U2") (pin "N5") (pinfunction "IO_L49P_D3_2_N5") (pintype "bidirectional"))
    )
    (net (code "191") (name "unconnected-(U2C-IO_L62N_D6_2-PadL7)") (class "Default")
      (node (ref "U2") (pin "L7") (pinfunction "IO_L62N_D6_2_L7") (pintype "bidirectional"))
    )
    (net (code "192") (name "unconnected-(U2C-IO_L62P_D5_2-PadL8)") (class "Default")
      (node (ref "U2") (pin "L8") (pinfunction "IO_L62P_D5_2_L8") (pintype "bidirectional"))
    )
    (net (code "193") (name "unconnected-(U2C-IO_L63N_2-PadT4)") (class "Default")
      (node (ref "U2") (pin "T4") (pinfunction "IO_L63N_2_T4") (pintype "bidirectional"))
    )
    (net (code "194") (name "unconnected-(U2C-IO_L63P_2-PadP4)") (class "Default")
      (node (ref "U2") (pin "P4") (pinfunction "IO_L63P_2_P4") (pintype "bidirectional"))
    )
    (net (code "195") (name "unconnected-(U2C-IO_L64N_D9_2-PadN6)") (class "Default")
      (node (ref "U2") (pin "N6") (pinfunction "IO_L64N_D9_2_N6") (pintype "bidirectional"))
    )
    (net (code "196") (name "unconnected-(U2C-IO_L64P_D8_2-PadM6)") (class "Default")
      (node (ref "U2") (pin "M6") (pinfunction "IO_L64P_D8_2_M6") (pintype "bidirectional"))
    )
    (net (code "197") (name "unconnected-(U2D-IO_L34N_M3UDQSN_3-PadN1)") (class "Default")
      (node (ref "U2") (pin "N1") (pinfunction "IO_L34N_M3UDQSN_3_N1") (pintype "bidirectional"))
    )
    (net (code "198") (name "unconnected-(U2D-IO_L34P_M3UDQS_3-PadN3)") (class "Default")
      (node (ref "U2") (pin "N3") (pinfunction "IO_L34P_M3UDQS_3_N3") (pintype "bidirectional"))
    )
    (net (code "199") (name "unconnected-(U2D-IO_L36N_M3DQ9_3-PadL1)") (class "Default")
      (node (ref "U2") (pin "L1") (pinfunction "IO_L36N_M3DQ9_3_L1") (pintype "bidirectional"))
    )
    (net (code "200") (name "unconnected-(U2D-IO_L36P_M3DQ8_3-PadL3)") (class "Default")
      (node (ref "U2") (pin "L3") (pinfunction "IO_L36P_M3DQ8_3_L3") (pintype "bidirectional"))
    )
    (net (code "201") (name "unconnected-(U2D-IO_L38N_M3DQ3_3-PadJ1)") (class "Default")
      (node (ref "U2") (pin "J1") (pinfunction "IO_L38N_M3DQ3_3_J1") (pintype "bidirectional"))
    )
    (net (code "202") (name "unconnected-(U2D-IO_L38P_M3DQ2_3-PadJ3)") (class "Default")
      (node (ref "U2") (pin "J3") (pinfunction "IO_L38P_M3DQ2_3_J3") (pintype "bidirectional"))
    )
    (net (code "203") (name "unconnected-(U2D-IO_L39N_M3LDQSN_3-PadH1)") (class "Default")
      (node (ref "U2") (pin "H1") (pinfunction "IO_L39N_M3LDQSN_3_H1") (pintype "bidirectional"))
    )
    (net (code "204") (name "unconnected-(U2D-IO_L39P_M3LDQS_3-PadH2)") (class "Default")
      (node (ref "U2") (pin "H2") (pinfunction "IO_L39P_M3LDQS_3_H2") (pintype "bidirectional"))
    )
    (net (code "205") (name "unconnected-(U2D-IO_L40N_M3DQ7_3-PadG1)") (class "Default")
      (node (ref "U2") (pin "G1") (pinfunction "IO_L40N_M3DQ7_3_G1") (pintype "bidirectional"))
    )
    (net (code "206") (name "unconnected-(U2D-IO_L40P_M3DQ6_3-PadG3)") (class "Default")
      (node (ref "U2") (pin "G3") (pinfunction "IO_L40P_M3DQ6_3_G3") (pintype "bidirectional"))
    )
    (net (code "207") (name "unconnected-(U2D-IO_L47N_M3A1_3-PadK6)") (class "Default")
      (node (ref "U2") (pin "K6") (pinfunction "IO_L47N_M3A1_3_K6") (pintype "bidirectional"))
    )
    (net (code "208") (name "unconnected-(U2D-IO_L47P_M3A0_3-PadK5)") (class "Default")
      (node (ref "U2") (pin "K5") (pinfunction "IO_L47P_M3A0_3_K5") (pintype "bidirectional"))
    )
    (net (code "209") (name "unconnected-(U2D-IO_L48N_M3BA1_3-PadC2)") (class "Default")
      (node (ref "U2") (pin "C2") (pinfunction "IO_L48N_M3BA1_3_C2") (pintype "bidirectional"))
    )
    (net (code "210") (name "unconnected-(U2D-IO_L48P_M3BA0_3-PadC3)") (class "Default")
      (node (ref "U2") (pin "C3") (pinfunction "IO_L48P_M3BA0_3_C3") (pintype "bidirectional"))
    )
    (net (code "211") (name "unconnected-(U2D-IO_L53N_M3A12_3-PadF3)") (class "Default")
      (node (ref "U2") (pin "F3") (pinfunction "IO_L53N_M3A12_3_F3") (pintype "bidirectional"))
    )
    (net (code "212") (name "unconnected-(U2D-IO_L53P_M3CKE_3-PadF4)") (class "Default")
      (node (ref "U2") (pin "F4") (pinfunction "IO_L53P_M3CKE_3_F4") (pintype "bidirectional"))
    )
    (net (code "213") (name "unconnected-(U4-PG-Pad6)") (class "Default")
      (node (ref "U4") (pin "6") (pinfunction "PG_6") (pintype "bidirectional"))
    )
    (net (code "214") (name "unconnected-(U5-PG-Pad6)") (class "Default")
      (node (ref "U5") (pin "6") (pinfunction "PG_6") (pintype "bidirectional"))
    )
    (net (code "215") (name "unconnected-(U7-PG-Pad6)") (class "Default")
      (node (ref "U7") (pin "6") (pinfunction "PG_6") (pintype "bidirectional"))
    )
    (net (code "216") (name "unconnected-(X1-TRI-Pad1)") (class "Default")
      (node (ref "X1") (pin "1") (pinfunction "TRI_1") (pintype "input"))
    )
  )
)
